# main_full_64.net
KiCad netlist of a schematic drawn in EAGLE
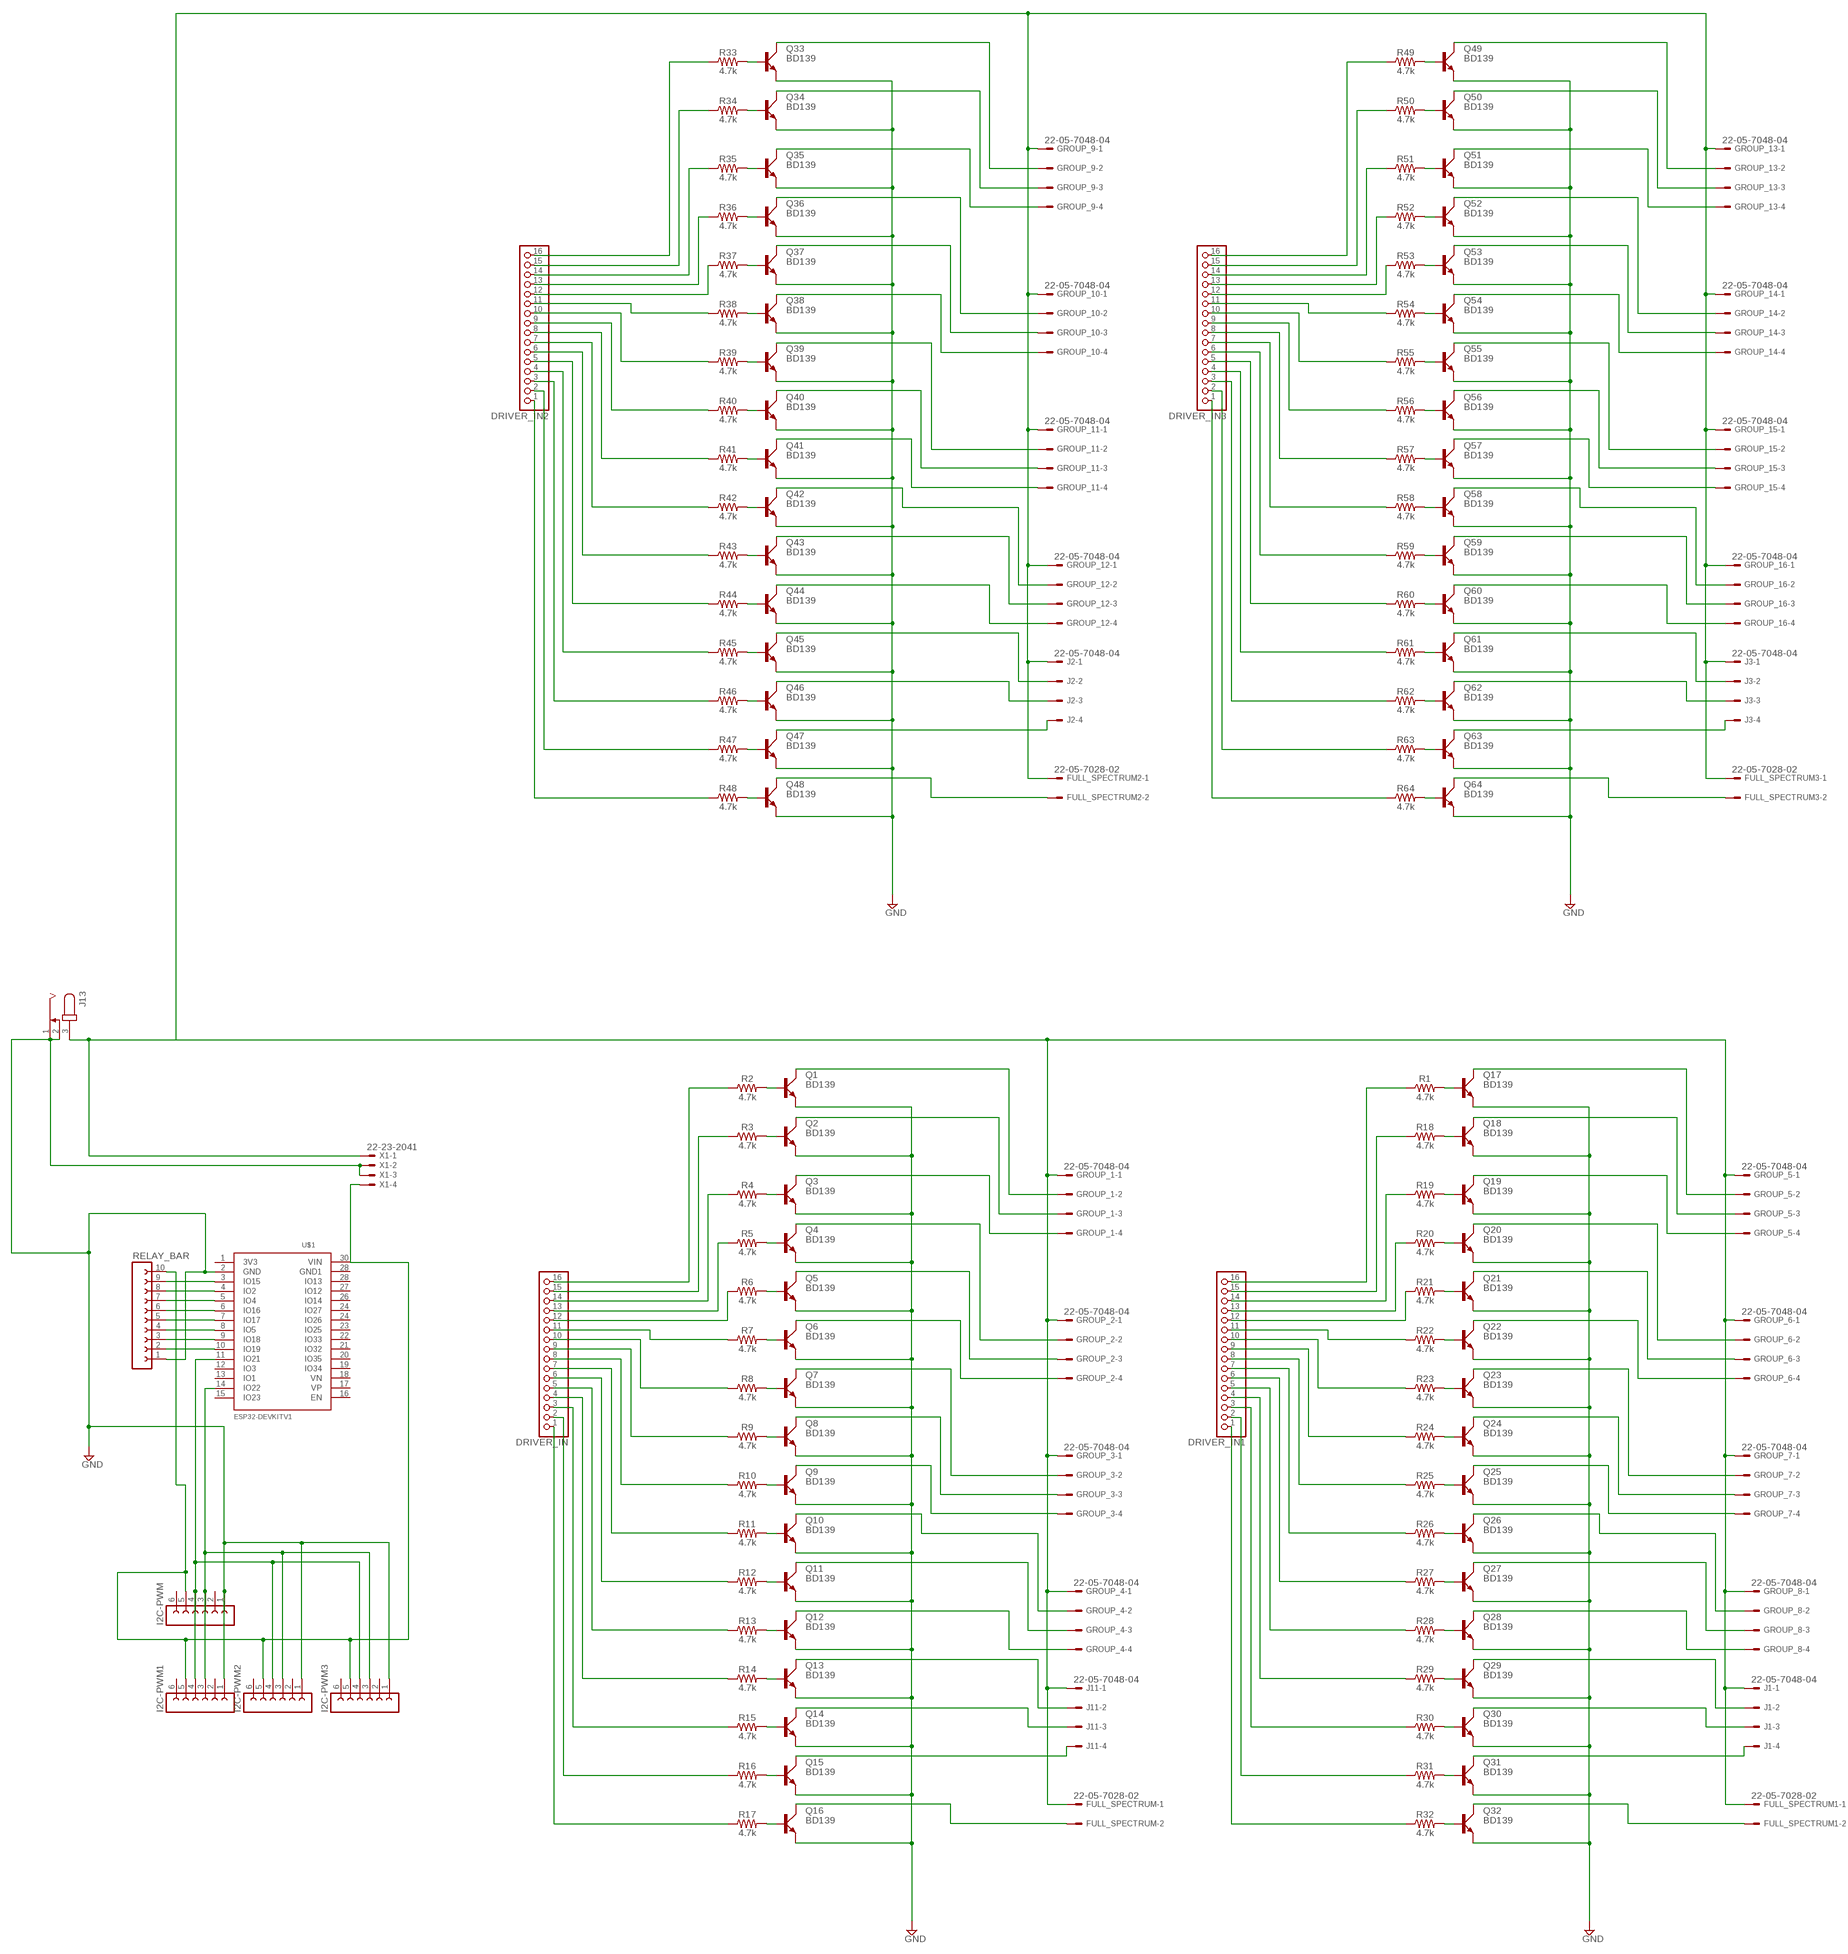
[diagram p0: schematic, sheet 1]

(export (version "E")
  (design (tool "Eeschema 10.0.6"))
  (components
    (comp (ref "DRIVER_IN")
      (value "PINHD-1X16/90")
      (footprint "eagle-import:1X16_90")
      (libsource (lib "eagle-import") (part "PINHD-1X16/90"))
    )
    (comp (ref "DRIVER_IN1")
      (value "PINHD-1X16/90")
      (footprint "eagle-import:1X16_90")
      (libsource (lib "eagle-import") (part "PINHD-1X16/90"))
    )
    (comp (ref "DRIVER_IN2")
      (value "PINHD-1X16/90")
      (footprint "eagle-import:1X16_90")
      (libsource (lib "eagle-import") (part "PINHD-1X16/90"))
    )
    (comp (ref "DRIVER_IN3")
      (value "PINHD-1X16/90")
      (footprint "eagle-import:1X16_90")
      (libsource (lib "eagle-import") (part "PINHD-1X16/90"))
    )
    (comp (ref "FULL_SPECTRUM")
      (value "22-05-7028-02")
      (footprint "eagle-import:7395-02")
      (fields (field (name "MF") "MOLEX"))
      (libsource (lib "eagle-import") (part "22-?-0205-7028"))
    )
    (comp (ref "FULL_SPECTRUM1")
      (value "22-05-7028-02")
      (footprint "eagle-import:7395-02")
      (fields (field (name "MF") "MOLEX"))
      (libsource (lib "eagle-import") (part "22-?-0205-7028"))
    )
    (comp (ref "FULL_SPECTRUM2")
      (value "22-05-7028-02")
      (footprint "eagle-import:7395-02")
      (fields (field (name "MF") "MOLEX"))
      (libsource (lib "eagle-import") (part "22-?-0205-7028"))
    )
    (comp (ref "FULL_SPECTRUM3")
      (value "22-05-7028-02")
      (footprint "eagle-import:7395-02")
      (fields (field (name "MF") "MOLEX"))
      (libsource (lib "eagle-import") (part "22-?-0205-7028"))
    )
    (comp (ref "GROUP_1")
      (value "22-05-7048-04")
      (footprint "eagle-import:7395-04")
      (fields (field (name "MF") "MOLEX"))
      (libsource (lib "eagle-import") (part "22-?-0405-7048"))
    )
    (comp (ref "GROUP_2")
      (value "22-05-7048-04")
      (footprint "eagle-import:7395-04")
      (fields (field (name "MF") "MOLEX"))
      (libsource (lib "eagle-import") (part "22-?-0405-7048"))
    )
    (comp (ref "GROUP_3")
      (value "22-05-7048-04")
      (footprint "eagle-import:7395-04")
      (fields (field (name "MF") "MOLEX"))
      (libsource (lib "eagle-import") (part "22-?-0405-7048"))
    )
    (comp (ref "GROUP_4")
      (value "22-05-7048-04")
      (footprint "eagle-import:7395-04")
      (fields (field (name "MF") "MOLEX"))
      (libsource (lib "eagle-import") (part "22-?-0405-7048"))
    )
    (comp (ref "GROUP_5")
      (value "22-05-7048-04")
      (footprint "eagle-import:7395-04")
      (fields (field (name "MF") "MOLEX"))
      (libsource (lib "eagle-import") (part "22-?-0405-7048"))
    )
    (comp (ref "GROUP_6")
      (value "22-05-7048-04")
      (footprint "eagle-import:7395-04")
      (fields (field (name "MF") "MOLEX"))
      (libsource (lib "eagle-import") (part "22-?-0405-7048"))
    )
    (comp (ref "GROUP_7")
      (value "22-05-7048-04")
      (footprint "eagle-import:7395-04")
      (fields (field (name "MF") "MOLEX"))
      (libsource (lib "eagle-import") (part "22-?-0405-7048"))
    )
    (comp (ref "GROUP_8")
      (value "22-05-7048-04")
      (footprint "eagle-import:7395-04")
      (fields (field (name "MF") "MOLEX"))
      (libsource (lib "eagle-import") (part "22-?-0405-7048"))
    )
    (comp (ref "GROUP_9")
      (value "22-05-7048-04")
      (footprint "eagle-import:7395-04")
      (fields (field (name "MF") "MOLEX"))
      (libsource (lib "eagle-import") (part "22-?-0405-7048"))
    )
    (comp (ref "GROUP_10")
      (value "22-05-7048-04")
      (footprint "eagle-import:7395-04")
      (fields (field (name "MF") "MOLEX"))
      (libsource (lib "eagle-import") (part "22-?-0405-7048"))
    )
    (comp (ref "GROUP_11")
      (value "22-05-7048-04")
      (footprint "eagle-import:7395-04")
      (fields (field (name "MF") "MOLEX"))
      (libsource (lib "eagle-import") (part "22-?-0405-7048"))
    )
    (comp (ref "GROUP_12")
      (value "22-05-7048-04")
      (footprint "eagle-import:7395-04")
      (fields (field (name "MF") "MOLEX"))
      (libsource (lib "eagle-import") (part "22-?-0405-7048"))
    )
    (comp (ref "GROUP_13")
      (value "22-05-7048-04")
      (footprint "eagle-import:7395-04")
      (fields (field (name "MF") "MOLEX"))
      (libsource (lib "eagle-import") (part "22-?-0405-7048"))
    )
    (comp (ref "GROUP_14")
      (value "22-05-7048-04")
      (footprint "eagle-import:7395-04")
      (fields (field (name "MF") "MOLEX"))
      (libsource (lib "eagle-import") (part "22-?-0405-7048"))
    )
    (comp (ref "GROUP_15")
      (value "22-05-7048-04")
      (footprint "eagle-import:7395-04")
      (fields (field (name "MF") "MOLEX"))
      (libsource (lib "eagle-import") (part "22-?-0405-7048"))
    )
    (comp (ref "GROUP_16")
      (value "22-05-7048-04")
      (footprint "eagle-import:7395-04")
      (fields (field (name "MF") "MOLEX"))
      (libsource (lib "eagle-import") (part "22-?-0405-7048"))
    )
    (comp (ref "I2C-PWM")
      (value "FE06W")
      (footprint "eagle-import:FE06W")
      (libsource (lib "eagle-import") (part "FE06W"))
    )
    (comp (ref "I2C-PWM1")
      (value "FE06W")
      (footprint "eagle-import:FE06W")
      (libsource (lib "eagle-import") (part "FE06W"))
    )
    (comp (ref "I2C-PWM2")
      (value "FE06W")
      (footprint "eagle-import:FE06W")
      (libsource (lib "eagle-import") (part "FE06W"))
    )
    (comp (ref "I2C-PWM3")
      (value "FE06W")
      (footprint "eagle-import:FE06W")
      (libsource (lib "eagle-import") (part "FE06W"))
    )
    (comp (ref "J1")
      (value "22-05-7048-04")
      (footprint "eagle-import:7395-04")
      (fields (field (name "MF") "MOLEX"))
      (libsource (lib "eagle-import") (part "22-?-0405-7048"))
    )
    (comp (ref "J2")
      (value "22-05-7048-04")
      (footprint "eagle-import:7395-04")
      (fields (field (name "MF") "MOLEX"))
      (libsource (lib "eagle-import") (part "22-?-0405-7048"))
    )
    (comp (ref "J3")
      (value "22-05-7048-04")
      (footprint "eagle-import:7395-04")
      (fields (field (name "MF") "MOLEX"))
      (libsource (lib "eagle-import") (part "22-?-0405-7048"))
    )
    (comp (ref "J11")
      (value "22-05-7048-04")
      (footprint "eagle-import:7395-04")
      (fields (field (name "MF") "MOLEX"))
      (libsource (lib "eagle-import") (part "22-?-0405-7048"))
    )
    (comp (ref "J13")
      (value "JACK-PLUG0")
      (footprint "eagle-import:SPC4077")
      (libsource (lib "eagle-import") (part "JACK-PLUG0"))
    )
    (comp (ref "Q1")
      (value "BD139")
      (footprint "eagle-import:TO126AV")
      (libsource (lib "eagle-import") (part "BD139"))
    )
    (comp (ref "Q2")
      (value "BD139")
      (footprint "eagle-import:TO126AV")
      (libsource (lib "eagle-import") (part "BD139"))
    )
    (comp (ref "Q3")
      (value "BD139")
      (footprint "eagle-import:TO126AV")
      (libsource (lib "eagle-import") (part "BD139"))
    )
    (comp (ref "Q4")
      (value "BD139")
      (footprint "eagle-import:TO126AV")
      (libsource (lib "eagle-import") (part "BD139"))
    )
    (comp (ref "Q5")
      (value "BD139")
      (footprint "eagle-import:TO126AV")
      (libsource (lib "eagle-import") (part "BD139"))
    )
    (comp (ref "Q6")
      (value "BD139")
      (footprint "eagle-import:TO126AV")
      (libsource (lib "eagle-import") (part "BD139"))
    )
    (comp (ref "Q7")
      (value "BD139")
      (footprint "eagle-import:TO126AV")
      (libsource (lib "eagle-import") (part "BD139"))
    )
    (comp (ref "Q8")
      (value "BD139")
      (footprint "eagle-import:TO126AV")
      (libsource (lib "eagle-import") (part "BD139"))
    )
    (comp (ref "Q9")
      (value "BD139")
      (footprint "eagle-import:TO126AV")
      (libsource (lib "eagle-import") (part "BD139"))
    )
    (comp (ref "Q10")
      (value "BD139")
      (footprint "eagle-import:TO126AV")
      (libsource (lib "eagle-import") (part "BD139"))
    )
    (comp (ref "Q11")
      (value "BD139")
      (footprint "eagle-import:TO126AV")
      (libsource (lib "eagle-import") (part "BD139"))
    )
    (comp (ref "Q12")
      (value "BD139")
      (footprint "eagle-import:TO126AV")
      (libsource (lib "eagle-import") (part "BD139"))
    )
    (comp (ref "Q13")
      (value "BD139")
      (footprint "eagle-import:TO126AV")
      (libsource (lib "eagle-import") (part "BD139"))
    )
    (comp (ref "Q14")
      (value "BD139")
      (footprint "eagle-import:TO126AV")
      (libsource (lib "eagle-import") (part "BD139"))
    )
    (comp (ref "Q15")
      (value "BD139")
      (footprint "eagle-import:TO126AV")
      (libsource (lib "eagle-import") (part "BD139"))
    )
    (comp (ref "Q16")
      (value "BD139")
      (footprint "eagle-import:TO126AV")
      (libsource (lib "eagle-import") (part "BD139"))
    )
    (comp (ref "Q17")
      (value "BD139")
      (footprint "eagle-import:TO126AV")
      (libsource (lib "eagle-import") (part "BD139"))
    )
    (comp (ref "Q18")
      (value "BD139")
      (footprint "eagle-import:TO126AV")
      (libsource (lib "eagle-import") (part "BD139"))
    )
    (comp (ref "Q19")
      (value "BD139")
      (footprint "eagle-import:TO126AV")
      (libsource (lib "eagle-import") (part "BD139"))
    )
    (comp (ref "Q20")
      (value "BD139")
      (footprint "eagle-import:TO126AV")
      (libsource (lib "eagle-import") (part "BD139"))
    )
    (comp (ref "Q21")
      (value "BD139")
      (footprint "eagle-import:TO126AV")
      (libsource (lib "eagle-import") (part "BD139"))
    )
    (comp (ref "Q22")
      (value "BD139")
      (footprint "eagle-import:TO126AV")
      (libsource (lib "eagle-import") (part "BD139"))
    )
    (comp (ref "Q23")
      (value "BD139")
      (footprint "eagle-import:TO126AV")
      (libsource (lib "eagle-import") (part "BD139"))
    )
    (comp (ref "Q24")
      (value "BD139")
      (footprint "eagle-import:TO126AV")
      (libsource (lib "eagle-import") (part "BD139"))
    )
    (comp (ref "Q25")
      (value "BD139")
      (footprint "eagle-import:TO126AV")
      (libsource (lib "eagle-import") (part "BD139"))
    )
    (comp (ref "Q26")
      (value "BD139")
      (footprint "eagle-import:TO126AV")
      (libsource (lib "eagle-import") (part "BD139"))
    )
    (comp (ref "Q27")
      (value "BD139")
      (footprint "eagle-import:TO126AV")
      (libsource (lib "eagle-import") (part "BD139"))
    )
    (comp (ref "Q28")
      (value "BD139")
      (footprint "eagle-import:TO126AV")
      (libsource (lib "eagle-import") (part "BD139"))
    )
    (comp (ref "Q29")
      (value "BD139")
      (footprint "eagle-import:TO126AV")
      (libsource (lib "eagle-import") (part "BD139"))
    )
    (comp (ref "Q30")
      (value "BD139")
      (footprint "eagle-import:TO126AV")
      (libsource (lib "eagle-import") (part "BD139"))
    )
    (comp (ref "Q31")
      (value "BD139")
      (footprint "eagle-import:TO126AV")
      (libsource (lib "eagle-import") (part "BD139"))
    )
    (comp (ref "Q32")
      (value "BD139")
      (footprint "eagle-import:TO126AV")
      (libsource (lib "eagle-import") (part "BD139"))
    )
    (comp (ref "Q33")
      (value "BD139")
      (footprint "eagle-import:TO126AV")
      (libsource (lib "eagle-import") (part "BD139"))
    )
    (comp (ref "Q34")
      (value "BD139")
      (footprint "eagle-import:TO126AV")
      (libsource (lib "eagle-import") (part "BD139"))
    )
    (comp (ref "Q35")
      (value "BD139")
      (footprint "eagle-import:TO126AV")
      (libsource (lib "eagle-import") (part "BD139"))
    )
    (comp (ref "Q36")
      (value "BD139")
      (footprint "eagle-import:TO126AV")
      (libsource (lib "eagle-import") (part "BD139"))
    )
    (comp (ref "Q37")
      (value "BD139")
      (footprint "eagle-import:TO126AV")
      (libsource (lib "eagle-import") (part "BD139"))
    )
    (comp (ref "Q38")
      (value "BD139")
      (footprint "eagle-import:TO126AV")
      (libsource (lib "eagle-import") (part "BD139"))
    )
    (comp (ref "Q39")
      (value "BD139")
      (footprint "eagle-import:TO126AV")
      (libsource (lib "eagle-import") (part "BD139"))
    )
    (comp (ref "Q40")
      (value "BD139")
      (footprint "eagle-import:TO126AV")
      (libsource (lib "eagle-import") (part "BD139"))
    )
    (comp (ref "Q41")
      (value "BD139")
      (footprint "eagle-import:TO126AV")
      (libsource (lib "eagle-import") (part "BD139"))
    )
    (comp (ref "Q42")
      (value "BD139")
      (footprint "eagle-import:TO126AV")
      (libsource (lib "eagle-import") (part "BD139"))
    )
    (comp (ref "Q43")
      (value "BD139")
      (footprint "eagle-import:TO126AV")
      (libsource (lib "eagle-import") (part "BD139"))
    )
    (comp (ref "Q44")
      (value "BD139")
      (footprint "eagle-import:TO126AV")
      (libsource (lib "eagle-import") (part "BD139"))
    )
    (comp (ref "Q45")
      (value "BD139")
      (footprint "eagle-import:TO126AV")
      (libsource (lib "eagle-import") (part "BD139"))
    )
    (comp (ref "Q46")
      (value "BD139")
      (footprint "eagle-import:TO126AV")
      (libsource (lib "eagle-import") (part "BD139"))
    )
    (comp (ref "Q47")
      (value "BD139")
      (footprint "eagle-import:TO126AV")
      (libsource (lib "eagle-import") (part "BD139"))
    )
    (comp (ref "Q48")
      (value "BD139")
      (footprint "eagle-import:TO126AV")
      (libsource (lib "eagle-import") (part "BD139"))
    )
    (comp (ref "Q49")
      (value "BD139")
      (footprint "eagle-import:TO126AV")
      (libsource (lib "eagle-import") (part "BD139"))
    )
    (comp (ref "Q50")
      (value "BD139")
      (footprint "eagle-import:TO126AV")
      (libsource (lib "eagle-import") (part "BD139"))
    )
    (comp (ref "Q51")
      (value "BD139")
      (footprint "eagle-import:TO126AV")
      (libsource (lib "eagle-import") (part "BD139"))
    )
    (comp (ref "Q52")
      (value "BD139")
      (footprint "eagle-import:TO126AV")
      (libsource (lib "eagle-import") (part "BD139"))
    )
    (comp (ref "Q53")
      (value "BD139")
      (footprint "eagle-import:TO126AV")
      (libsource (lib "eagle-import") (part "BD139"))
    )
    (comp (ref "Q54")
      (value "BD139")
      (footprint "eagle-import:TO126AV")
      (libsource (lib "eagle-import") (part "BD139"))
    )
    (comp (ref "Q55")
      (value "BD139")
      (footprint "eagle-import:TO126AV")
      (libsource (lib "eagle-import") (part "BD139"))
    )
    (comp (ref "Q56")
      (value "BD139")
      (footprint "eagle-import:TO126AV")
      (libsource (lib "eagle-import") (part "BD139"))
    )
    (comp (ref "Q57")
      (value "BD139")
      (footprint "eagle-import:TO126AV")
      (libsource (lib "eagle-import") (part "BD139"))
    )
    (comp (ref "Q58")
      (value "BD139")
      (footprint "eagle-import:TO126AV")
      (libsource (lib "eagle-import") (part "BD139"))
    )
    (comp (ref "Q59")
      (value "BD139")
      (footprint "eagle-import:TO126AV")
      (libsource (lib "eagle-import") (part "BD139"))
    )
    (comp (ref "Q60")
      (value "BD139")
      (footprint "eagle-import:TO126AV")
      (libsource (lib "eagle-import") (part "BD139"))
    )
    (comp (ref "Q61")
      (value "BD139")
      (footprint "eagle-import:TO126AV")
      (libsource (lib "eagle-import") (part "BD139"))
    )
    (comp (ref "Q62")
      (value "BD139")
      (footprint "eagle-import:TO126AV")
      (libsource (lib "eagle-import") (part "BD139"))
    )
    (comp (ref "Q63")
      (value "BD139")
      (footprint "eagle-import:TO126AV")
      (libsource (lib "eagle-import") (part "BD139"))
    )
    (comp (ref "Q64")
      (value "BD139")
      (footprint "eagle-import:TO126AV")
      (libsource (lib "eagle-import") (part "BD139"))
    )
    (comp (ref "R1")
      (value "4.7k")
      (footprint "eagle-import:0603")
      (libsource (lib "eagle-import") (part "4.7KOHM-0603-1/10W-1%"))
    )
    (comp (ref "R2")
      (value "4.7k")
      (footprint "eagle-import:0603")
      (libsource (lib "eagle-import") (part "4.7KOHM-0603-1/10W-1%"))
    )
    (comp (ref "R3")
      (value "4.7k")
      (footprint "eagle-import:0603")
      (libsource (lib "eagle-import") (part "4.7KOHM-0603-1/10W-1%"))
    )
    (comp (ref "R4")
      (value "4.7k")
      (footprint "eagle-import:0603")
      (libsource (lib "eagle-import") (part "4.7KOHM-0603-1/10W-1%"))
    )
    (comp (ref "R5")
      (value "4.7k")
      (footprint "eagle-import:0603")
      (libsource (lib "eagle-import") (part "4.7KOHM-0603-1/10W-1%"))
    )
    (comp (ref "R6")
      (value "4.7k")
      (footprint "eagle-import:0603")
      (libsource (lib "eagle-import") (part "4.7KOHM-0603-1/10W-1%"))
    )
    (comp (ref "R7")
      (value "4.7k")
      (footprint "eagle-import:0603")
      (libsource (lib "eagle-import") (part "4.7KOHM-0603-1/10W-1%"))
    )
    (comp (ref "R8")
      (value "4.7k")
      (footprint "eagle-import:0603")
      (libsource (lib "eagle-import") (part "4.7KOHM-0603-1/10W-1%"))
    )
    (comp (ref "R9")
      (value "4.7k")
      (footprint "eagle-import:0603")
      (libsource (lib "eagle-import") (part "4.7KOHM-0603-1/10W-1%"))
    )
    (comp (ref "R10")
      (value "4.7k")
      (footprint "eagle-import:0603")
      (libsource (lib "eagle-import") (part "4.7KOHM-0603-1/10W-1%"))
    )
    (comp (ref "R11")
      (value "4.7k")
      (footprint "eagle-import:0603")
      (libsource (lib "eagle-import") (part "4.7KOHM-0603-1/10W-1%"))
    )
    (comp (ref "R12")
      (value "4.7k")
      (footprint "eagle-import:0603")
      (libsource (lib "eagle-import") (part "4.7KOHM-0603-1/10W-1%"))
    )
    (comp (ref "R13")
      (value "4.7k")
      (footprint "eagle-import:0603")
      (libsource (lib "eagle-import") (part "4.7KOHM-0603-1/10W-1%"))
    )
    (comp (ref "R14")
      (value "4.7k")
      (footprint "eagle-import:0603")
      (libsource (lib "eagle-import") (part "4.7KOHM-0603-1/10W-1%"))
    )
    (comp (ref "R15")
      (value "4.7k")
      (footprint "eagle-import:0603")
      (libsource (lib "eagle-import") (part "4.7KOHM-0603-1/10W-1%"))
    )
    (comp (ref "R16")
      (value "4.7k")
      (footprint "eagle-import:0603")
      (libsource (lib "eagle-import") (part "4.7KOHM-0603-1/10W-1%"))
    )
    (comp (ref "R17")
      (value "4.7k")
      (footprint "eagle-import:0603")
      (libsource (lib "eagle-import") (part "4.7KOHM-0603-1/10W-1%"))
    )
    (comp (ref "R18")
      (value "4.7k")
      (footprint "eagle-import:0603")
      (libsource (lib "eagle-import") (part "4.7KOHM-0603-1/10W-1%"))
    )
    (comp (ref "R19")
      (value "4.7k")
      (footprint "eagle-import:0603")
      (libsource (lib "eagle-import") (part "4.7KOHM-0603-1/10W-1%"))
    )
    (comp (ref "R20")
      (value "4.7k")
      (footprint "eagle-import:0603")
      (libsource (lib "eagle-import") (part "4.7KOHM-0603-1/10W-1%"))
    )
    (comp (ref "R21")
      (value "4.7k")
      (footprint "eagle-import:0603")
      (libsource (lib "eagle-import") (part "4.7KOHM-0603-1/10W-1%"))
    )
    (comp (ref "R22")
      (value "4.7k")
      (footprint "eagle-import:0603")
      (libsource (lib "eagle-import") (part "4.7KOHM-0603-1/10W-1%"))
    )
    (comp (ref "R23")
      (value "4.7k")
      (footprint "eagle-import:0603")
      (libsource (lib "eagle-import") (part "4.7KOHM-0603-1/10W-1%"))
    )
    (comp (ref "R24")
      (value "4.7k")
      (footprint "eagle-import:0603")
      (libsource (lib "eagle-import") (part "4.7KOHM-0603-1/10W-1%"))
    )
    (comp (ref "R25")
      (value "4.7k")
      (footprint "eagle-import:0603")
      (libsource (lib "eagle-import") (part "4.7KOHM-0603-1/10W-1%"))
    )
    (comp (ref "R26")
      (value "4.7k")
      (footprint "eagle-import:0603")
      (libsource (lib "eagle-import") (part "4.7KOHM-0603-1/10W-1%"))
    )
    (comp (ref "R27")
      (value "4.7k")
      (footprint "eagle-import:0603")
      (libsource (lib "eagle-import") (part "4.7KOHM-0603-1/10W-1%"))
    )
    (comp (ref "R28")
      (value "4.7k")
      (footprint "eagle-import:0603")
      (libsource (lib "eagle-import") (part "4.7KOHM-0603-1/10W-1%"))
    )
    (comp (ref "R29")
      (value "4.7k")
      (footprint "eagle-import:0603")
      (libsource (lib "eagle-import") (part "4.7KOHM-0603-1/10W-1%"))
    )
    (comp (ref "R30")
      (value "4.7k")
      (footprint "eagle-import:0603")
      (libsource (lib "eagle-import") (part "4.7KOHM-0603-1/10W-1%"))
    )
    (comp (ref "R31")
      (value "4.7k")
      (footprint "eagle-import:0603")
      (libsource (lib "eagle-import") (part "4.7KOHM-0603-1/10W-1%"))
    )
    (comp (ref "R32")
      (value "4.7k")
      (footprint "eagle-import:0603")
      (libsource (lib "eagle-import") (part "4.7KOHM-0603-1/10W-1%"))
    )
    (comp (ref "R33")
      (value "4.7k")
      (footprint "eagle-import:0603")
      (libsource (lib "eagle-import") (part "4.7KOHM-0603-1/10W-1%"))
    )
    (comp (ref "R34")
      (value "4.7k")
      (footprint "eagle-import:0603")
      (libsource (lib "eagle-import") (part "4.7KOHM-0603-1/10W-1%"))
    )
    (comp (ref "R35")
      (value "4.7k")
      (footprint "eagle-import:0603")
      (libsource (lib "eagle-import") (part "4.7KOHM-0603-1/10W-1%"))
    )
    (comp (ref "R36")
      (value "4.7k")
      (footprint "eagle-import:0603")
      (libsource (lib "eagle-import") (part "4.7KOHM-0603-1/10W-1%"))
    )
    (comp (ref "R37")
      (value "4.7k")
      (footprint "eagle-import:0603")
      (libsource (lib "eagle-import") (part "4.7KOHM-0603-1/10W-1%"))
    )
    (comp (ref "R38")
      (value "4.7k")
      (footprint "eagle-import:0603")
      (libsource (lib "eagle-import") (part "4.7KOHM-0603-1/10W-1%"))
    )
    (comp (ref "R39")
      (value "4.7k")
      (footprint "eagle-import:0603")
      (libsource (lib "eagle-import") (part "4.7KOHM-0603-1/10W-1%"))
    )
    (comp (ref "R40")
      (value "4.7k")
      (footprint "eagle-import:0603")
      (libsource (lib "eagle-import") (part "4.7KOHM-0603-1/10W-1%"))
    )
    (comp (ref "R41")
      (value "4.7k")
      (footprint "eagle-import:0603")
      (libsource (lib "eagle-import") (part "4.7KOHM-0603-1/10W-1%"))
    )
    (comp (ref "R42")
      (value "4.7k")
      (footprint "eagle-import:0603")
      (libsource (lib "eagle-import") (part "4.7KOHM-0603-1/10W-1%"))
    )
    (comp (ref "R43")
      (value "4.7k")
      (footprint "eagle-import:0603")
      (libsource (lib "eagle-import") (part "4.7KOHM-0603-1/10W-1%"))
    )
    (comp (ref "R44")
      (value "4.7k")
      (footprint "eagle-import:0603")
      (libsource (lib "eagle-import") (part "4.7KOHM-0603-1/10W-1%"))
    )
    (comp (ref "R45")
      (value "4.7k")
      (footprint "eagle-import:0603")
      (libsource (lib "eagle-import") (part "4.7KOHM-0603-1/10W-1%"))
    )
    (comp (ref "R46")
      (value "4.7k")
      (footprint "eagle-import:0603")
      (libsource (lib "eagle-import") (part "4.7KOHM-0603-1/10W-1%"))
    )
    (comp (ref "R47")
      (value "4.7k")
      (footprint "eagle-import:0603")
      (libsource (lib "eagle-import") (part "4.7KOHM-0603-1/10W-1%"))
    )
    (comp (ref "R48")
      (value "4.7k")
      (footprint "eagle-import:0603")
      (libsource (lib "eagle-import") (part "4.7KOHM-0603-1/10W-1%"))
    )
    (comp (ref "R49")
      (value "4.7k")
      (footprint "eagle-import:0603")
      (libsource (lib "eagle-import") (part "4.7KOHM-0603-1/10W-1%"))
    )
    (comp (ref "R50")
      (value "4.7k")
      (footprint "eagle-import:0603")
      (libsource (lib "eagle-import") (part "4.7KOHM-0603-1/10W-1%"))
    )
    (comp (ref "R51")
      (value "4.7k")
      (footprint "eagle-import:0603")
      (libsource (lib "eagle-import") (part "4.7KOHM-0603-1/10W-1%"))
    )
    (comp (ref "R52")
      (value "4.7k")
      (footprint "eagle-import:0603")
      (libsource (lib "eagle-import") (part "4.7KOHM-0603-1/10W-1%"))
    )
    (comp (ref "R53")
      (value "4.7k")
      (footprint "eagle-import:0603")
      (libsource (lib "eagle-import") (part "4.7KOHM-0603-1/10W-1%"))
    )
    (comp (ref "R54")
      (value "4.7k")
      (footprint "eagle-import:0603")
      (libsource (lib "eagle-import") (part "4.7KOHM-0603-1/10W-1%"))
    )
    (comp (ref "R55")
      (value "4.7k")
      (footprint "eagle-import:0603")
      (libsource (lib "eagle-import") (part "4.7KOHM-0603-1/10W-1%"))
    )
    (comp (ref "R56")
      (value "4.7k")
      (footprint "eagle-import:0603")
      (libsource (lib "eagle-import") (part "4.7KOHM-0603-1/10W-1%"))
    )
    (comp (ref "R57")
      (value "4.7k")
      (footprint "eagle-import:0603")
      (libsource (lib "eagle-import") (part "4.7KOHM-0603-1/10W-1%"))
    )
    (comp (ref "R58")
      (value "4.7k")
      (footprint "eagle-import:0603")
      (libsource (lib "eagle-import") (part "4.7KOHM-0603-1/10W-1%"))
    )
    (comp (ref "R59")
      (value "4.7k")
      (footprint "eagle-import:0603")
      (libsource (lib "eagle-import") (part "4.7KOHM-0603-1/10W-1%"))
    )
    (comp (ref "R60")
      (value "4.7k")
      (footprint "eagle-import:0603")
      (libsource (lib "eagle-import") (part "4.7KOHM-0603-1/10W-1%"))
    )
    (comp (ref "R61")
      (value "4.7k")
      (footprint "eagle-import:0603")
      (libsource (lib "eagle-import") (part "4.7KOHM-0603-1/10W-1%"))
    )
    (comp (ref "R62")
      (value "4.7k")
      (footprint "eagle-import:0603")
      (libsource (lib "eagle-import") (part "4.7KOHM-0603-1/10W-1%"))
    )
    (comp (ref "R63")
      (value "4.7k")
      (footprint "eagle-import:0603")
      (libsource (lib "eagle-import") (part "4.7KOHM-0603-1/10W-1%"))
    )
    (comp (ref "R64")
      (value "4.7k")
      (footprint "eagle-import:0603")
      (libsource (lib "eagle-import") (part "4.7KOHM-0603-1/10W-1%"))
    )
    (comp (ref "RELAY_BAR")
      (value "FE10W")
      (footprint "eagle-import:FE10W")
      (libsource (lib "eagle-import") (part "FE10W"))
    )
    (comp (ref "U$1")
      (value "ESP32DEVKITV1")
      (footprint "eagle-import:ESP32-DEVKITV1")
      (libsource (lib "eagle-import") (part "ESP32DEVKITV1"))
    )
    (comp (ref "X1")
      (value "22-23-2041")
      (footprint "eagle-import:22-23-2041")
      (fields (field (name "MF") "MOLEX"))
      (libsource (lib "eagle-import") (part "22-23-2041"))
    )
  )
  (nets
    (net (code "1") (name "GND") (class "Default")
      (node (ref "I2C-PWM") (pin "1") (pinfunction "1_1") (pintype "passive"))
      (node (ref "I2C-PWM1") (pin "1") (pinfunction "1_1") (pintype "passive"))
      (node (ref "I2C-PWM2") (pin "1") (pinfunction "1_1") (pintype "passive"))
      (node (ref "I2C-PWM3") (pin "1") (pinfunction "1_1") (pintype "passive"))
      (node (ref "J13") (pin "1") (pinfunction "1_1") (pintype "passive"))
      (node (ref "J13") (pin "2") (pinfunction "2_2") (pintype "passive"))
      (node (ref "Q1") (pin "E") (pinfunction "E_E") (pintype "passive"))
      (node (ref "Q10") (pin "E") (pinfunction "E_E") (pintype "passive"))
      (node (ref "Q11") (pin "E") (pinfunction "E_E") (pintype "passive"))
      (node (ref "Q12") (pin "E") (pinfunction "E_E") (pintype "passive"))
      (node (ref "Q13") (pin "E") (pinfunction "E_E") (pintype "passive"))
      (node (ref "Q14") (pin "E") (pinfunction "E_E") (pintype "passive"))
      (node (ref "Q15") (pin "E") (pinfunction "E_E") (pintype "passive"))
      (node (ref "Q16") (pin "E") (pinfunction "E_E") (pintype "passive"))
      (node (ref "Q17") (pin "E") (pinfunction "E_E") (pintype "passive"))
      (node (ref "Q18") (pin "E") (pinfunction "E_E") (pintype "passive"))
      (node (ref "Q19") (pin "E") (pinfunction "E_E") (pintype "passive"))
      (node (ref "Q2") (pin "E") (pinfunction "E_E") (pintype "passive"))
      (node (ref "Q20") (pin "E") (pinfunction "E_E") (pintype "passive"))
      (node (ref "Q21") (pin "E") (pinfunction "E_E") (pintype "passive"))
      (node (ref "Q22") (pin "E") (pinfunction "E_E") (pintype "passive"))
      (node (ref "Q23") (pin "E") (pinfunction "E_E") (pintype "passive"))
      (node (ref "Q24") (pin "E") (pinfunction "E_E") (pintype "passive"))
      (node (ref "Q25") (pin "E") (pinfunction "E_E") (pintype "passive"))
      (node (ref "Q26") (pin "E") (pinfunction "E_E") (pintype "passive"))
      (node (ref "Q27") (pin "E") (pinfunction "E_E") (pintype "passive"))
      (node (ref "Q28") (pin "E") (pinfunction "E_E") (pintype "passive"))
      (node (ref "Q29") (pin "E") (pinfunction "E_E") (pintype "passive"))
      (node (ref "Q3") (pin "E") (pinfunction "E_E") (pintype "passive"))
      (node (ref "Q30") (pin "E") (pinfunction "E_E") (pintype "passive"))
      (node (ref "Q31") (pin "E") (pinfunction "E_E") (pintype "passive"))
      (node (ref "Q32") (pin "E") (pinfunction "E_E") (pintype "passive"))
      (node (ref "Q33") (pin "E") (pinfunction "E_E") (pintype "passive"))
      (node (ref "Q34") (pin "E") (pinfunction "E_E") (pintype "passive"))
      (node (ref "Q35") (pin "E") (pinfunction "E_E") (pintype "passive"))
      (node (ref "Q36") (pin "E") (pinfunction "E_E") (pintype "passive"))
      (node (ref "Q37") (pin "E") (pinfunction "E_E") (pintype "passive"))
      (node (ref "Q38") (pin "E") (pinfunction "E_E") (pintype "passive"))
      (node (ref "Q39") (pin "E") (pinfunction "E_E") (pintype "passive"))
      (node (ref "Q4") (pin "E") (pinfunction "E_E") (pintype "passive"))
      (node (ref "Q40") (pin "E") (pinfunction "E_E") (pintype "passive"))
      (node (ref "Q41") (pin "E") (pinfunction "E_E") (pintype "passive"))
      (node (ref "Q42") (pin "E") (pinfunction "E_E") (pintype "passive"))
      (node (ref "Q43") (pin "E") (pinfunction "E_E") (pintype "passive"))
      (node (ref "Q44") (pin "E") (pinfunction "E_E") (pintype "passive"))
      (node (ref "Q45") (pin "E") (pinfunction "E_E") (pintype "passive"))
      (node (ref "Q46") (pin "E") (pinfunction "E_E") (pintype "passive"))
      (node (ref "Q47") (pin "E") (pinfunction "E_E") (pintype "passive"))
      (node (ref "Q48") (pin "E") (pinfunction "E_E") (pintype "passive"))
      (node (ref "Q49") (pin "E") (pinfunction "E_E") (pintype "passive"))
      (node (ref "Q5") (pin "E") (pinfunction "E_E") (pintype "passive"))
      (node (ref "Q50") (pin "E") (pinfunction "E_E") (pintype "passive"))
      (node (ref "Q51") (pin "E") (pinfunction "E_E") (pintype "passive"))
      (node (ref "Q52") (pin "E") (pinfunction "E_E") (pintype "passive"))
      (node (ref "Q53") (pin "E") (pinfunction "E_E") (pintype "passive"))
      (node (ref "Q54") (pin "E") (pinfunction "E_E") (pintype "passive"))
      (node (ref "Q55") (pin "E") (pinfunction "E_E") (pintype "passive"))
      (node (ref "Q56") (pin "E") (pinfunction "E_E") (pintype "passive"))
      (node (ref "Q57") (pin "E") (pinfunction "E_E") (pintype "passive"))
      (node (ref "Q58") (pin "E") (pinfunction "E_E") (pintype "passive"))
      (node (ref "Q59") (pin "E") (pinfunction "E_E") (pintype "passive"))
      (node (ref "Q6") (pin "E") (pinfunction "E_E") (pintype "passive"))
      (node (ref "Q60") (pin "E") (pinfunction "E_E") (pintype "passive"))
      (node (ref "Q61") (pin "E") (pinfunction "E_E") (pintype "passive"))
      (node (ref "Q62") (pin "E") (pinfunction "E_E") (pintype "passive"))
      (node (ref "Q63") (pin "E") (pinfunction "E_E") (pintype "passive"))
      (node (ref "Q64") (pin "E") (pinfunction "E_E") (pintype "passive"))
      (node (ref "Q7") (pin "E") (pinfunction "E_E") (pintype "passive"))
      (node (ref "Q8") (pin "E") (pinfunction "E_E") (pintype "passive"))
      (node (ref "Q9") (pin "E") (pinfunction "E_E") (pintype "passive"))
      (node (ref "RELAY_BAR") (pin "1") (pinfunction "1_1") (pintype "passive"))
      (node (ref "U$1") (pin "2") (pinfunction "GND_2") (pintype "bidirectional"))
      (node (ref "X1") (pin "2") (pinfunction "S_2") (pintype "passive"))
      (node (ref "X1") (pin "3") (pinfunction "S_3") (pintype "passive"))
    )
    (net (code "2") (name "Net-(DRIVER_IN-Pad1)") (class "Default")
      (node (ref "DRIVER_IN") (pin "1") (pinfunction "1_1") (pintype "passive"))
      (node (ref "R17") (pin "1") (pinfunction "1_1") (pintype "passive"))
    )
    (net (code "3") (name "Net-(DRIVER_IN-Pad2)") (class "Default")
      (node (ref "DRIVER_IN") (pin "2") (pinfunction "2_2") (pintype "passive"))
      (node (ref "R16") (pin "1") (pinfunction "1_1") (pintype "passive"))
    )
    (net (code "4") (name "Net-(DRIVER_IN-Pad3)") (class "Default")
      (node (ref "DRIVER_IN") (pin "3") (pinfunction "3_3") (pintype "passive"))
      (node (ref "R15") (pin "1") (pinfunction "1_1") (pintype "passive"))
    )
    (net (code "5") (name "Net-(DRIVER_IN-Pad4)") (class "Default")
      (node (ref "DRIVER_IN") (pin "4") (pinfunction "4_4") (pintype "passive"))
      (node (ref "R14") (pin "1") (pinfunction "1_1") (pintype "passive"))
    )
    (net (code "6") (name "Net-(DRIVER_IN-Pad5)") (class "Default")
      (node (ref "DRIVER_IN") (pin "5") (pinfunction "5_5") (pintype "passive"))
      (node (ref "R13") (pin "1") (pinfunction "1_1") (pintype "passive"))
    )
    (net (code "7") (name "Net-(DRIVER_IN-Pad6)") (class "Default")
      (node (ref "DRIVER_IN") (pin "6") (pinfunction "6_6") (pintype "passive"))
      (node (ref "R12") (pin "1") (pinfunction "1_1") (pintype "passive"))
    )
    (net (code "8") (name "Net-(DRIVER_IN-Pad7)") (class "Default")
      (node (ref "DRIVER_IN") (pin "7") (pinfunction "7_7") (pintype "passive"))
      (node (ref "R11") (pin "1") (pinfunction "1_1") (pintype "passive"))
    )
    (net (code "9") (name "Net-(DRIVER_IN-Pad8)") (class "Default")
      (node (ref "DRIVER_IN") (pin "8") (pinfunction "8_8") (pintype "passive"))
      (node (ref "R10") (pin "1") (pinfunction "1_1") (pintype "passive"))
    )
    (net (code "10") (name "Net-(DRIVER_IN-Pad9)") (class "Default")
      (node (ref "DRIVER_IN") (pin "9") (pinfunction "9_9") (pintype "passive"))
      (node (ref "R9") (pin "1") (pinfunction "1_1") (pintype "passive"))
    )
    (net (code "11") (name "Net-(DRIVER_IN-Pad10)") (class "Default")
      (node (ref "DRIVER_IN") (pin "10") (pinfunction "10_10") (pintype "passive"))
      (node (ref "R8") (pin "1") (pinfunction "1_1") (pintype "passive"))
    )
    (net (code "12") (name "Net-(DRIVER_IN-Pad11)") (class "Default")
      (node (ref "DRIVER_IN") (pin "11") (pinfunction "11_11") (pintype "passive"))
      (node (ref "R7") (pin "1") (pinfunction "1_1") (pintype "passive"))
    )
    (net (code "13") (name "Net-(DRIVER_IN-Pad12)") (class "Default")
      (node (ref "DRIVER_IN") (pin "12") (pinfunction "12_12") (pintype "passive"))
      (node (ref "R6") (pin "1") (pinfunction "1_1") (pintype "passive"))
    )
    (net (code "14") (name "Net-(DRIVER_IN-Pad13)") (class "Default")
      (node (ref "DRIVER_IN") (pin "13") (pinfunction "13_13") (pintype "passive"))
      (node (ref "R5") (pin "1") (pinfunction "1_1") (pintype "passive"))
    )
    (net (code "15") (name "Net-(DRIVER_IN-Pad14)") (class "Default")
      (node (ref "DRIVER_IN") (pin "14") (pinfunction "14_14") (pintype "passive"))
      (node (ref "R4") (pin "1") (pinfunction "1_1") (pintype "passive"))
    )
    (net (code "16") (name "Net-(DRIVER_IN-Pad15)") (class "Default")
      (node (ref "DRIVER_IN") (pin "15") (pinfunction "15_15") (pintype "passive"))
      (node (ref "R3") (pin "1") (pinfunction "1_1") (pintype "passive"))
    )
    (net (code "17") (name "Net-(DRIVER_IN-Pad16)") (class "Default")
      (node (ref "DRIVER_IN") (pin "16") (pinfunction "16_16") (pintype "passive"))
      (node (ref "R2") (pin "1") (pinfunction "1_1") (pintype "passive"))
    )
    (net (code "18") (name "Net-(DRIVER_IN1-Pad1)") (class "Default")
      (node (ref "DRIVER_IN1") (pin "1") (pinfunction "1_1") (pintype "passive"))
      (node (ref "R32") (pin "1") (pinfunction "1_1") (pintype "passive"))
    )
    (net (code "19") (name "Net-(DRIVER_IN1-Pad2)") (class "Default")
      (node (ref "DRIVER_IN1") (pin "2") (pinfunction "2_2") (pintype "passive"))
      (node (ref "R31") (pin "1") (pinfunction "1_1") (pintype "passive"))
    )
    (net (code "20") (name "Net-(DRIVER_IN1-Pad3)") (class "Default")
      (node (ref "DRIVER_IN1") (pin "3") (pinfunction "3_3") (pintype "passive"))
      (node (ref "R30") (pin "1") (pinfunction "1_1") (pintype "passive"))
    )
    (net (code "21") (name "Net-(DRIVER_IN1-Pad4)") (class "Default")
      (node (ref "DRIVER_IN1") (pin "4") (pinfunction "4_4") (pintype "passive"))
      (node (ref "R29") (pin "1") (pinfunction "1_1") (pintype "passive"))
    )
    (net (code "22") (name "Net-(DRIVER_IN1-Pad5)") (class "Default")
      (node (ref "DRIVER_IN1") (pin "5") (pinfunction "5_5") (pintype "passive"))
      (node (ref "R28") (pin "1") (pinfunction "1_1") (pintype "passive"))
    )
    (net (code "23") (name "Net-(DRIVER_IN1-Pad6)") (class "Default")
      (node (ref "DRIVER_IN1") (pin "6") (pinfunction "6_6") (pintype "passive"))
      (node (ref "R27") (pin "1") (pinfunction "1_1") (pintype "passive"))
    )
    (net (code "24") (name "Net-(DRIVER_IN1-Pad7)") (class "Default")
      (node (ref "DRIVER_IN1") (pin "7") (pinfunction "7_7") (pintype "passive"))
      (node (ref "R26") (pin "1") (pinfunction "1_1") (pintype "passive"))
    )
    (net (code "25") (name "Net-(DRIVER_IN1-Pad8)") (class "Default")
      (node (ref "DRIVER_IN1") (pin "8") (pinfunction "8_8") (pintype "passive"))
      (node (ref "R25") (pin "1") (pinfunction "1_1") (pintype "passive"))
    )
    (net (code "26") (name "Net-(DRIVER_IN1-Pad9)") (class "Default")
      (node (ref "DRIVER_IN1") (pin "9") (pinfunction "9_9") (pintype "passive"))
      (node (ref "R24") (pin "1") (pinfunction "1_1") (pintype "passive"))
    )
    (net (code "27") (name "Net-(DRIVER_IN1-Pad10)") (class "Default")
      (node (ref "DRIVER_IN1") (pin "10") (pinfunction "10_10") (pintype "passive"))
      (node (ref "R23") (pin "1") (pinfunction "1_1") (pintype "passive"))
    )
    (net (code "28") (name "Net-(DRIVER_IN1-Pad11)") (class "Default")
      (node (ref "DRIVER_IN1") (pin "11") (pinfunction "11_11") (pintype "passive"))
      (node (ref "R22") (pin "1") (pinfunction "1_1") (pintype "passive"))
    )
    (net (code "29") (name "Net-(DRIVER_IN1-Pad12)") (class "Default")
      (node (ref "DRIVER_IN1") (pin "12") (pinfunction "12_12") (pintype "passive"))
      (node (ref "R21") (pin "1") (pinfunction "1_1") (pintype "passive"))
    )
    (net (code "30") (name "Net-(DRIVER_IN1-Pad13)") (class "Default")
      (node (ref "DRIVER_IN1") (pin "13") (pinfunction "13_13") (pintype "passive"))
      (node (ref "R20") (pin "1") (pinfunction "1_1") (pintype "passive"))
    )
    (net (code "31") (name "Net-(DRIVER_IN1-Pad14)") (class "Default")
      (node (ref "DRIVER_IN1") (pin "14") (pinfunction "14_14") (pintype "passive"))
      (node (ref "R19") (pin "1") (pinfunction "1_1") (pintype "passive"))
    )
    (net (code "32") (name "Net-(DRIVER_IN1-Pad15)") (class "Default")
      (node (ref "DRIVER_IN1") (pin "15") (pinfunction "15_15") (pintype "passive"))
      (node (ref "R18") (pin "1") (pinfunction "1_1") (pintype "passive"))
    )
    (net (code "33") (name "Net-(DRIVER_IN1-Pad16)") (class "Default")
      (node (ref "DRIVER_IN1") (pin "16") (pinfunction "16_16") (pintype "passive"))
      (node (ref "R1") (pin "1") (pinfunction "1_1") (pintype "passive"))
    )
    (net (code "34") (name "Net-(DRIVER_IN2-Pad1)") (class "Default")
      (node (ref "DRIVER_IN2") (pin "1") (pinfunction "1_1") (pintype "passive"))
      (node (ref "R48") (pin "1") (pinfunction "1_1") (pintype "passive"))
    )
    (net (code "35") (name "Net-(DRIVER_IN2-Pad2)") (class "Default")
      (node (ref "DRIVER_IN2") (pin "2") (pinfunction "2_2") (pintype "passive"))
      (node (ref "R47") (pin "1") (pinfunction "1_1") (pintype "passive"))
    )
    (net (code "36") (name "Net-(DRIVER_IN2-Pad3)") (class "Default")
      (node (ref "DRIVER_IN2") (pin "3") (pinfunction "3_3") (pintype "passive"))
      (node (ref "R46") (pin "1") (pinfunction "1_1") (pintype "passive"))
    )
    (net (code "37") (name "Net-(DRIVER_IN2-Pad4)") (class "Default")
      (node (ref "DRIVER_IN2") (pin "4") (pinfunction "4_4") (pintype "passive"))
      (node (ref "R45") (pin "1") (pinfunction "1_1") (pintype "passive"))
    )
    (net (code "38") (name "Net-(DRIVER_IN2-Pad5)") (class "Default")
      (node (ref "DRIVER_IN2") (pin "5") (pinfunction "5_5") (pintype "passive"))
      (node (ref "R44") (pin "1") (pinfunction "1_1") (pintype "passive"))
    )
    (net (code "39") (name "Net-(DRIVER_IN2-Pad6)") (class "Default")
      (node (ref "DRIVER_IN2") (pin "6") (pinfunction "6_6") (pintype "passive"))
      (node (ref "R43") (pin "1") (pinfunction "1_1") (pintype "passive"))
    )
    (net (code "40") (name "Net-(DRIVER_IN2-Pad7)") (class "Default")
      (node (ref "DRIVER_IN2") (pin "7") (pinfunction "7_7") (pintype "passive"))
      (node (ref "R42") (pin "1") (pinfunction "1_1") (pintype "passive"))
    )
    (net (code "41") (name "Net-(DRIVER_IN2-Pad8)") (class "Default")
      (node (ref "DRIVER_IN2") (pin "8") (pinfunction "8_8") (pintype "passive"))
      (node (ref "R41") (pin "1") (pinfunction "1_1") (pintype "passive"))
    )
    (net (code "42") (name "Net-(DRIVER_IN2-Pad9)") (class "Default")
      (node (ref "DRIVER_IN2") (pin "9") (pinfunction "9_9") (pintype "passive"))
      (node (ref "R40") (pin "1") (pinfunction "1_1") (pintype "passive"))
    )
    (net (code "43") (name "Net-(DRIVER_IN2-Pad10)") (class "Default")
      (node (ref "DRIVER_IN2") (pin "10") (pinfunction "10_10") (pintype "passive"))
      (node (ref "R39") (pin "1") (pinfunction "1_1") (pintype "passive"))
    )
    (net (code "44") (name "Net-(DRIVER_IN2-Pad11)") (class "Default")
      (node (ref "DRIVER_IN2") (pin "11") (pinfunction "11_11") (pintype "passive"))
      (node (ref "R38") (pin "1") (pinfunction "1_1") (pintype "passive"))
    )
    (net (code "45") (name "Net-(DRIVER_IN2-Pad12)") (class "Default")
      (node (ref "DRIVER_IN2") (pin "12") (pinfunction "12_12") (pintype "passive"))
      (node (ref "R37") (pin "1") (pinfunction "1_1") (pintype "passive"))
    )
    (net (code "46") (name "Net-(DRIVER_IN2-Pad13)") (class "Default")
      (node (ref "DRIVER_IN2") (pin "13") (pinfunction "13_13") (pintype "passive"))
      (node (ref "R36") (pin "1") (pinfunction "1_1") (pintype "passive"))
    )
    (net (code "47") (name "Net-(DRIVER_IN2-Pad14)") (class "Default")
      (node (ref "DRIVER_IN2") (pin "14") (pinfunction "14_14") (pintype "passive"))
      (node (ref "R35") (pin "1") (pinfunction "1_1") (pintype "passive"))
    )
    (net (code "48") (name "Net-(DRIVER_IN2-Pad15)") (class "Default")
      (node (ref "DRIVER_IN2") (pin "15") (pinfunction "15_15") (pintype "passive"))
      (node (ref "R34") (pin "1") (pinfunction "1_1") (pintype "passive"))
    )
    (net (code "49") (name "Net-(DRIVER_IN2-Pad16)") (class "Default")
      (node (ref "DRIVER_IN2") (pin "16") (pinfunction "16_16") (pintype "passive"))
      (node (ref "R33") (pin "1") (pinfunction "1_1") (pintype "passive"))
    )
    (net (code "50") (name "Net-(DRIVER_IN3-Pad1)") (class "Default")
      (node (ref "DRIVER_IN3") (pin "1") (pinfunction "1_1") (pintype "passive"))
      (node (ref "R64") (pin "1") (pinfunction "1_1") (pintype "passive"))
    )
    (net (code "51") (name "Net-(DRIVER_IN3-Pad2)") (class "Default")
      (node (ref "DRIVER_IN3") (pin "2") (pinfunction "2_2") (pintype "passive"))
      (node (ref "R63") (pin "1") (pinfunction "1_1") (pintype "passive"))
    )
    (net (code "52") (name "Net-(DRIVER_IN3-Pad3)") (class "Default")
      (node (ref "DRIVER_IN3") (pin "3") (pinfunction "3_3") (pintype "passive"))
      (node (ref "R62") (pin "1") (pinfunction "1_1") (pintype "passive"))
    )
    (net (code "53") (name "Net-(DRIVER_IN3-Pad4)") (class "Default")
      (node (ref "DRIVER_IN3") (pin "4") (pinfunction "4_4") (pintype "passive"))
      (node (ref "R61") (pin "1") (pinfunction "1_1") (pintype "passive"))
    )
    (net (code "54") (name "Net-(DRIVER_IN3-Pad5)") (class "Default")
      (node (ref "DRIVER_IN3") (pin "5") (pinfunction "5_5") (pintype "passive"))
      (node (ref "R60") (pin "1") (pinfunction "1_1") (pintype "passive"))
    )
    (net (code "55") (name "Net-(DRIVER_IN3-Pad6)") (class "Default")
      (node (ref "DRIVER_IN3") (pin "6") (pinfunction "6_6") (pintype "passive"))
      (node (ref "R59") (pin "1") (pinfunction "1_1") (pintype "passive"))
    )
    (net (code "56") (name "Net-(DRIVER_IN3-Pad7)") (class "Default")
      (node (ref "DRIVER_IN3") (pin "7") (pinfunction "7_7") (pintype "passive"))
      (node (ref "R58") (pin "1") (pinfunction "1_1") (pintype "passive"))
    )
    (net (code "57") (name "Net-(DRIVER_IN3-Pad8)") (class "Default")
      (node (ref "DRIVER_IN3") (pin "8") (pinfunction "8_8") (pintype "passive"))
      (node (ref "R57") (pin "1") (pinfunction "1_1") (pintype "passive"))
    )
    (net (code "58") (name "Net-(DRIVER_IN3-Pad9)") (class "Default")
      (node (ref "DRIVER_IN3") (pin "9") (pinfunction "9_9") (pintype "passive"))
      (node (ref "R56") (pin "1") (pinfunction "1_1") (pintype "passive"))
    )
    (net (code "59") (name "Net-(DRIVER_IN3-Pad10)") (class "Default")
      (node (ref "DRIVER_IN3") (pin "10") (pinfunction "10_10") (pintype "passive"))
      (node (ref "R55") (pin "1") (pinfunction "1_1") (pintype "passive"))
    )
    (net (code "60") (name "Net-(DRIVER_IN3-Pad11)") (class "Default")
      (node (ref "DRIVER_IN3") (pin "11") (pinfunction "11_11") (pintype "passive"))
      (node (ref "R54") (pin "1") (pinfunction "1_1") (pintype "passive"))
    )
    (net (code "61") (name "Net-(DRIVER_IN3-Pad12)") (class "Default")
      (node (ref "DRIVER_IN3") (pin "12") (pinfunction "12_12") (pintype "passive"))
      (node (ref "R53") (pin "1") (pinfunction "1_1") (pintype "passive"))
    )
    (net (code "62") (name "Net-(DRIVER_IN3-Pad13)") (class "Default")
      (node (ref "DRIVER_IN3") (pin "13") (pinfunction "13_13") (pintype "passive"))
      (node (ref "R52") (pin "1") (pinfunction "1_1") (pintype "passive"))
    )
    (net (code "63") (name "Net-(DRIVER_IN3-Pad14)") (class "Default")
      (node (ref "DRIVER_IN3") (pin "14") (pinfunction "14_14") (pintype "passive"))
      (node (ref "R51") (pin "1") (pinfunction "1_1") (pintype "passive"))
    )
    (net (code "64") (name "Net-(DRIVER_IN3-Pad15)") (class "Default")
      (node (ref "DRIVER_IN3") (pin "15") (pinfunction "15_15") (pintype "passive"))
      (node (ref "R50") (pin "1") (pinfunction "1_1") (pintype "passive"))
    )
    (net (code "65") (name "Net-(DRIVER_IN3-Pad16)") (class "Default")
      (node (ref "DRIVER_IN3") (pin "16") (pinfunction "16_16") (pintype "passive"))
      (node (ref "R49") (pin "1") (pinfunction "1_1") (pintype "passive"))
    )
    (net (code "66") (name "Net-(FULL_SPECTRUM1A-S)") (class "Default")
      (node (ref "FULL_SPECTRUM") (pin "1") (pinfunction "S_1") (pintype "passive"))
      (node (ref "FULL_SPECTRUM1") (pin "1") (pinfunction "S_1") (pintype "passive"))
      (node (ref "FULL_SPECTRUM2") (pin "1") (pinfunction "S_1") (pintype "passive"))
      (node (ref "FULL_SPECTRUM3") (pin "1") (pinfunction "S_1") (pintype "passive"))
      (node (ref "GROUP_1") (pin "1") (pinfunction "S_1") (pintype "passive"))
      (node (ref "GROUP_10") (pin "1") (pinfunction "S_1") (pintype "passive"))
      (node (ref "GROUP_11") (pin "1") (pinfunction "S_1") (pintype "passive"))
      (node (ref "GROUP_12") (pin "1") (pinfunction "S_1") (pintype "passive"))
      (node (ref "GROUP_13") (pin "1") (pinfunction "S_1") (pintype "passive"))
      (node (ref "GROUP_14") (pin "1") (pinfunction "S_1") (pintype "passive"))
      (node (ref "GROUP_15") (pin "1") (pinfunction "S_1") (pintype "passive"))
      (node (ref "GROUP_16") (pin "1") (pinfunction "S_1") (pintype "passive"))
      (node (ref "GROUP_2") (pin "1") (pinfunction "S_1") (pintype "passive"))
      (node (ref "GROUP_3") (pin "1") (pinfunction "S_1") (pintype "passive"))
      (node (ref "GROUP_4") (pin "1") (pinfunction "S_1") (pintype "passive"))
      (node (ref "GROUP_5") (pin "1") (pinfunction "S_1") (pintype "passive"))
      (node (ref "GROUP_6") (pin "1") (pinfunction "S_1") (pintype "passive"))
      (node (ref "GROUP_7") (pin "1") (pinfunction "S_1") (pintype "passive"))
      (node (ref "GROUP_8") (pin "1") (pinfunction "S_1") (pintype "passive"))
      (node (ref "GROUP_9") (pin "1") (pinfunction "S_1") (pintype "passive"))
      (node (ref "J1") (pin "1") (pinfunction "S_1") (pintype "passive"))
      (node (ref "J11") (pin "1") (pinfunction "S_1") (pintype "passive"))
      (node (ref "J13") (pin "3") (pinfunction "3_3") (pintype "passive"))
      (node (ref "J2") (pin "1") (pinfunction "S_1") (pintype "passive"))
      (node (ref "J3") (pin "1") (pinfunction "S_1") (pintype "passive"))
      (node (ref "X1") (pin "1") (pinfunction "S_1") (pintype "passive"))
    )
    (net (code "67") (name "Net-(FULL_SPECTRUM1B-S)") (class "Default")
      (node (ref "FULL_SPECTRUM1") (pin "2") (pinfunction "S_2") (pintype "passive"))
      (node (ref "Q32") (pin "C") (pinfunction "C_C") (pintype "passive"))
    )
    (net (code "68") (name "Net-(FULL_SPECTRUM2B-S)") (class "Default")
      (node (ref "FULL_SPECTRUM2") (pin "2") (pinfunction "S_2") (pintype "passive"))
      (node (ref "Q48") (pin "C") (pinfunction "C_C") (pintype "passive"))
    )
    (net (code "69") (name "Net-(FULL_SPECTRUM3B-S)") (class "Default")
      (node (ref "FULL_SPECTRUM3") (pin "2") (pinfunction "S_2") (pintype "passive"))
      (node (ref "Q64") (pin "C") (pinfunction "C_C") (pintype "passive"))
    )
    (net (code "70") (name "Net-(FULL_SPECTRUMB-S)") (class "Default")
      (node (ref "FULL_SPECTRUM") (pin "2") (pinfunction "S_2") (pintype "passive"))
      (node (ref "Q16") (pin "C") (pinfunction "C_C") (pintype "passive"))
    )
    (net (code "71") (name "Net-(GROUP_1B-S)") (class "Default")
      (node (ref "GROUP_1") (pin "2") (pinfunction "S_2") (pintype "passive"))
      (node (ref "Q1") (pin "C") (pinfunction "C_C") (pintype "passive"))
    )
    (net (code "72") (name "Net-(GROUP_1C-S)") (class "Default")
      (node (ref "GROUP_1") (pin "3") (pinfunction "S_3") (pintype "passive"))
      (node (ref "Q2") (pin "C") (pinfunction "C_C") (pintype "passive"))
    )
    (net (code "73") (name "Net-(GROUP_1D-S)") (class "Default")
      (node (ref "GROUP_1") (pin "4") (pinfunction "S_4") (pintype "passive"))
      (node (ref "Q3") (pin "C") (pinfunction "C_C") (pintype "passive"))
    )
    (net (code "74") (name "Net-(GROUP_2B-S)") (class "Default")
      (node (ref "GROUP_2") (pin "2") (pinfunction "S_2") (pintype "passive"))
      (node (ref "Q4") (pin "C") (pinfunction "C_C") (pintype "passive"))
    )
    (net (code "75") (name "Net-(GROUP_2C-S)") (class "Default")
      (node (ref "GROUP_2") (pin "3") (pinfunction "S_3") (pintype "passive"))
      (node (ref "Q5") (pin "C") (pinfunction "C_C") (pintype "passive"))
    )
    (net (code "76") (name "Net-(GROUP_2D-S)") (class "Default")
      (node (ref "GROUP_2") (pin "4") (pinfunction "S_4") (pintype "passive"))
      (node (ref "Q6") (pin "C") (pinfunction "C_C") (pintype "passive"))
    )
    (net (code "77") (name "Net-(GROUP_3B-S)") (class "Default")
      (node (ref "GROUP_3") (pin "2") (pinfunction "S_2") (pintype "passive"))
      (node (ref "Q7") (pin "C") (pinfunction "C_C") (pintype "passive"))
    )
    (net (code "78") (name "Net-(GROUP_3C-S)") (class "Default")
      (node (ref "GROUP_3") (pin "3") (pinfunction "S_3") (pintype "passive"))
      (node (ref "Q8") (pin "C") (pinfunction "C_C") (pintype "passive"))
    )
    (net (code "79") (name "Net-(GROUP_3D-S)") (class "Default")
      (node (ref "GROUP_3") (pin "4") (pinfunction "S_4") (pintype "passive"))
      (node (ref "Q9") (pin "C") (pinfunction "C_C") (pintype "passive"))
    )
    (net (code "80") (name "Net-(GROUP_4B-S)") (class "Default")
      (node (ref "GROUP_4") (pin "2") (pinfunction "S_2") (pintype "passive"))
      (node (ref "Q10") (pin "C") (pinfunction "C_C") (pintype "passive"))
    )
    (net (code "81") (name "Net-(GROUP_4C-S)") (class "Default")
      (node (ref "GROUP_4") (pin "3") (pinfunction "S_3") (pintype "passive"))
      (node (ref "Q11") (pin "C") (pinfunction "C_C") (pintype "passive"))
    )
    (net (code "82") (name "Net-(GROUP_4D-S)") (class "Default")
      (node (ref "GROUP_4") (pin "4") (pinfunction "S_4") (pintype "passive"))
      (node (ref "Q12") (pin "C") (pinfunction "C_C") (pintype "passive"))
    )
    (net (code "83") (name "Net-(GROUP_5B-S)") (class "Default")
      (node (ref "GROUP_5") (pin "2") (pinfunction "S_2") (pintype "passive"))
      (node (ref "Q17") (pin "C") (pinfunction "C_C") (pintype "passive"))
    )
    (net (code "84") (name "Net-(GROUP_5C-S)") (class "Default")
      (node (ref "GROUP_5") (pin "3") (pinfunction "S_3") (pintype "passive"))
      (node (ref "Q18") (pin "C") (pinfunction "C_C") (pintype "passive"))
    )
    (net (code "85") (name "Net-(GROUP_5D-S)") (class "Default")
      (node (ref "GROUP_5") (pin "4") (pinfunction "S_4") (pintype "passive"))
      (node (ref "Q19") (pin "C") (pinfunction "C_C") (pintype "passive"))
    )
    (net (code "86") (name "Net-(GROUP_6B-S)") (class "Default")
      (node (ref "GROUP_6") (pin "2") (pinfunction "S_2") (pintype "passive"))
      (node (ref "Q20") (pin "C") (pinfunction "C_C") (pintype "passive"))
    )
    (net (code "87") (name "Net-(GROUP_6C-S)") (class "Default")
      (node (ref "GROUP_6") (pin "3") (pinfunction "S_3") (pintype "passive"))
      (node (ref "Q21") (pin "C") (pinfunction "C_C") (pintype "passive"))
    )
    (net (code "88") (name "Net-(GROUP_6D-S)") (class "Default")
      (node (ref "GROUP_6") (pin "4") (pinfunction "S_4") (pintype "passive"))
      (node (ref "Q22") (pin "C") (pinfunction "C_C") (pintype "passive"))
    )
    (net (code "89") (name "Net-(GROUP_7B-S)") (class "Default")
      (node (ref "GROUP_7") (pin "2") (pinfunction "S_2") (pintype "passive"))
      (node (ref "Q23") (pin "C") (pinfunction "C_C") (pintype "passive"))
    )
    (net (code "90") (name "Net-(GROUP_7C-S)") (class "Default")
      (node (ref "GROUP_7") (pin "3") (pinfunction "S_3") (pintype "passive"))
      (node (ref "Q24") (pin "C") (pinfunction "C_C") (pintype "passive"))
    )
    (net (code "91") (name "Net-(GROUP_7D-S)") (class "Default")
      (node (ref "GROUP_7") (pin "4") (pinfunction "S_4") (pintype "passive"))
      (node (ref "Q25") (pin "C") (pinfunction "C_C") (pintype "passive"))
    )
    (net (code "92") (name "Net-(GROUP_8B-S)") (class "Default")
      (node (ref "GROUP_8") (pin "2") (pinfunction "S_2") (pintype "passive"))
      (node (ref "Q26") (pin "C") (pinfunction "C_C") (pintype "passive"))
    )
    (net (code "93") (name "Net-(GROUP_8C-S)") (class "Default")
      (node (ref "GROUP_8") (pin "3") (pinfunction "S_3") (pintype "passive"))
      (node (ref "Q27") (pin "C") (pinfunction "C_C") (pintype "passive"))
    )
    (net (code "94") (name "Net-(GROUP_8D-S)") (class "Default")
      (node (ref "GROUP_8") (pin "4") (pinfunction "S_4") (pintype "passive"))
      (node (ref "Q28") (pin "C") (pinfunction "C_C") (pintype "passive"))
    )
    (net (code "95") (name "Net-(GROUP_9B-S)") (class "Default")
      (node (ref "GROUP_9") (pin "2") (pinfunction "S_2") (pintype "passive"))
      (node (ref "Q33") (pin "C") (pinfunction "C_C") (pintype "passive"))
    )
    (net (code "96") (name "Net-(GROUP_9C-S)") (class "Default")
      (node (ref "GROUP_9") (pin "3") (pinfunction "S_3") (pintype "passive"))
      (node (ref "Q34") (pin "C") (pinfunction "C_C") (pintype "passive"))
    )
    (net (code "97") (name "Net-(GROUP_9D-S)") (class "Default")
      (node (ref "GROUP_9") (pin "4") (pinfunction "S_4") (pintype "passive"))
      (node (ref "Q35") (pin "C") (pinfunction "C_C") (pintype "passive"))
    )
    (net (code "98") (name "Net-(GROUP_10B-S)") (class "Default")
      (node (ref "GROUP_10") (pin "2") (pinfunction "S_2") (pintype "passive"))
      (node (ref "Q36") (pin "C") (pinfunction "C_C") (pintype "passive"))
    )
    (net (code "99") (name "Net-(GROUP_10C-S)") (class "Default")
      (node (ref "GROUP_10") (pin "3") (pinfunction "S_3") (pintype "passive"))
      (node (ref "Q37") (pin "C") (pinfunction "C_C") (pintype "passive"))
    )
    (net (code "100") (name "Net-(GROUP_10D-S)") (class "Default")
      (node (ref "GROUP_10") (pin "4") (pinfunction "S_4") (pintype "passive"))
      (node (ref "Q38") (pin "C") (pinfunction "C_C") (pintype "passive"))
    )
    (net (code "101") (name "Net-(GROUP_11B-S)") (class "Default")
      (node (ref "GROUP_11") (pin "2") (pinfunction "S_2") (pintype "passive"))
      (node (ref "Q39") (pin "C") (pinfunction "C_C") (pintype "passive"))
    )
    (net (code "102") (name "Net-(GROUP_11C-S)") (class "Default")
      (node (ref "GROUP_11") (pin "3") (pinfunction "S_3") (pintype "passive"))
      (node (ref "Q40") (pin "C") (pinfunction "C_C") (pintype "passive"))
    )
    (net (code "103") (name "Net-(GROUP_11D-S)") (class "Default")
      (node (ref "GROUP_11") (pin "4") (pinfunction "S_4") (pintype "passive"))
      (node (ref "Q41") (pin "C") (pinfunction "C_C") (pintype "passive"))
    )
    (net (code "104") (name "Net-(GROUP_12B-S)") (class "Default")
      (node (ref "GROUP_12") (pin "2") (pinfunction "S_2") (pintype "passive"))
      (node (ref "Q42") (pin "C") (pinfunction "C_C") (pintype "passive"))
    )
    (net (code "105") (name "Net-(GROUP_12C-S)") (class "Default")
      (node (ref "GROUP_12") (pin "3") (pinfunction "S_3") (pintype "passive"))
      (node (ref "Q43") (pin "C") (pinfunction "C_C") (pintype "passive"))
    )
    (net (code "106") (name "Net-(GROUP_12D-S)") (class "Default")
      (node (ref "GROUP_12") (pin "4") (pinfunction "S_4") (pintype "passive"))
      (node (ref "Q44") (pin "C") (pinfunction "C_C") (pintype "passive"))
    )
    (net (code "107") (name "Net-(GROUP_13B-S)") (class "Default")
      (node (ref "GROUP_13") (pin "2") (pinfunction "S_2") (pintype "passive"))
      (node (ref "Q49") (pin "C") (pinfunction "C_C") (pintype "passive"))
    )
    (net (code "108") (name "Net-(GROUP_13C-S)") (class "Default")
      (node (ref "GROUP_13") (pin "3") (pinfunction "S_3") (pintype "passive"))
      (node (ref "Q50") (pin "C") (pinfunction "C_C") (pintype "passive"))
    )
    (net (code "109") (name "Net-(GROUP_13D-S)") (class "Default")
      (node (ref "GROUP_13") (pin "4") (pinfunction "S_4") (pintype "passive"))
      (node (ref "Q51") (pin "C") (pinfunction "C_C") (pintype "passive"))
    )
    (net (code "110") (name "Net-(GROUP_14B-S)") (class "Default")
      (node (ref "GROUP_14") (pin "2") (pinfunction "S_2") (pintype "passive"))
      (node (ref "Q52") (pin "C") (pinfunction "C_C") (pintype "passive"))
    )
    (net (code "111") (name "Net-(GROUP_14C-S)") (class "Default")
      (node (ref "GROUP_14") (pin "3") (pinfunction "S_3") (pintype "passive"))
      (node (ref "Q53") (pin "C") (pinfunction "C_C") (pintype "passive"))
    )
    (net (code "112") (name "Net-(GROUP_14D-S)") (class "Default")
      (node (ref "GROUP_14") (pin "4") (pinfunction "S_4") (pintype "passive"))
      (node (ref "Q54") (pin "C") (pinfunction "C_C") (pintype "passive"))
    )
    (net (code "113") (name "Net-(GROUP_15B-S)") (class "Default")
      (node (ref "GROUP_15") (pin "2") (pinfunction "S_2") (pintype "passive"))
      (node (ref "Q55") (pin "C") (pinfunction "C_C") (pintype "passive"))
    )
    (net (code "114") (name "Net-(GROUP_15C-S)") (class "Default")
      (node (ref "GROUP_15") (pin "3") (pinfunction "S_3") (pintype "passive"))
      (node (ref "Q56") (pin "C") (pinfunction "C_C") (pintype "passive"))
    )
    (net (code "115") (name "Net-(GROUP_15D-S)") (class "Default")
      (node (ref "GROUP_15") (pin "4") (pinfunction "S_4") (pintype "passive"))
      (node (ref "Q57") (pin "C") (pinfunction "C_C") (pintype "passive"))
    )
    (net (code "116") (name "Net-(GROUP_16B-S)") (class "Default")
      (node (ref "GROUP_16") (pin "2") (pinfunction "S_2") (pintype "passive"))
      (node (ref "Q58") (pin "C") (pinfunction "C_C") (pintype "passive"))
    )
    (net (code "117") (name "Net-(GROUP_16C-S)") (class "Default")
      (node (ref "GROUP_16") (pin "3") (pinfunction "S_3") (pintype "passive"))
      (node (ref "Q59") (pin "C") (pinfunction "C_C") (pintype "passive"))
    )
    (net (code "118") (name "Net-(GROUP_16D-S)") (class "Default")
      (node (ref "GROUP_16") (pin "4") (pinfunction "S_4") (pintype "passive"))
      (node (ref "Q60") (pin "C") (pinfunction "C_C") (pintype "passive"))
    )
    (net (code "119") (name "Net-(J1B-S)") (class "Default")
      (node (ref "J1") (pin "2") (pinfunction "S_2") (pintype "passive"))
      (node (ref "Q29") (pin "C") (pinfunction "C_C") (pintype "passive"))
    )
    (net (code "120") (name "Net-(J1C-S)") (class "Default")
      (node (ref "J1") (pin "3") (pinfunction "S_3") (pintype "passive"))
      (node (ref "Q30") (pin "C") (pinfunction "C_C") (pintype "passive"))
    )
    (net (code "121") (name "Net-(J1D-S)") (class "Default")
      (node (ref "J1") (pin "4") (pinfunction "S_4") (pintype "passive"))
      (node (ref "Q31") (pin "C") (pinfunction "C_C") (pintype "passive"))
    )
    (net (code "122") (name "Net-(J2B-S)") (class "Default")
      (node (ref "J2") (pin "2") (pinfunction "S_2") (pintype "passive"))
      (node (ref "Q45") (pin "C") (pinfunction "C_C") (pintype "passive"))
    )
    (net (code "123") (name "Net-(J2C-S)") (class "Default")
      (node (ref "J2") (pin "3") (pinfunction "S_3") (pintype "passive"))
      (node (ref "Q46") (pin "C") (pinfunction "C_C") (pintype "passive"))
    )
    (net (code "124") (name "Net-(J2D-S)") (class "Default")
      (node (ref "J2") (pin "4") (pinfunction "S_4") (pintype "passive"))
      (node (ref "Q47") (pin "C") (pinfunction "C_C") (pintype "passive"))
    )
    (net (code "125") (name "Net-(J3B-S)") (class "Default")
      (node (ref "J3") (pin "2") (pinfunction "S_2") (pintype "passive"))
      (node (ref "Q61") (pin "C") (pinfunction "C_C") (pintype "passive"))
    )
    (net (code "126") (name "Net-(J3C-S)") (class "Default")
      (node (ref "J3") (pin "3") (pinfunction "S_3") (pintype "passive"))
      (node (ref "Q62") (pin "C") (pinfunction "C_C") (pintype "passive"))
    )
    (net (code "127") (name "Net-(J3D-S)") (class "Default")
      (node (ref "J3") (pin "4") (pinfunction "S_4") (pintype "passive"))
      (node (ref "Q63") (pin "C") (pinfunction "C_C") (pintype "passive"))
    )
    (net (code "128") (name "Net-(J11B-S)") (class "Default")
      (node (ref "J11") (pin "2") (pinfunction "S_2") (pintype "passive"))
      (node (ref "Q13") (pin "C") (pinfunction "C_C") (pintype "passive"))
    )
    (net (code "129") (name "Net-(J11C-S)") (class "Default")
      (node (ref "J11") (pin "3") (pinfunction "S_3") (pintype "passive"))
      (node (ref "Q14") (pin "C") (pinfunction "C_C") (pintype "passive"))
    )
    (net (code "130") (name "Net-(J11D-S)") (class "Default")
      (node (ref "J11") (pin "4") (pinfunction "S_4") (pintype "passive"))
      (node (ref "Q15") (pin "C") (pinfunction "C_C") (pintype "passive"))
    )
    (net (code "131") (name "Net-(Q1-PadB)") (class "Default")
      (node (ref "Q1") (pin "B") (pinfunction "B_B") (pintype "passive"))
      (node (ref "R2") (pin "2") (pinfunction "2_2") (pintype "passive"))
    )
    (net (code "132") (name "Net-(Q2-PadB)") (class "Default")
      (node (ref "Q2") (pin "B") (pinfunction "B_B") (pintype "passive"))
      (node (ref "R3") (pin "2") (pinfunction "2_2") (pintype "passive"))
    )
    (net (code "133") (name "Net-(Q3-PadB)") (class "Default")
      (node (ref "Q3") (pin "B") (pinfunction "B_B") (pintype "passive"))
      (node (ref "R4") (pin "2") (pinfunction "2_2") (pintype "passive"))
    )
    (net (code "134") (name "Net-(Q4-PadB)") (class "Default")
      (node (ref "Q4") (pin "B") (pinfunction "B_B") (pintype "passive"))
      (node (ref "R5") (pin "2") (pinfunction "2_2") (pintype "passive"))
    )
    (net (code "135") (name "Net-(Q5-PadB)") (class "Default")
      (node (ref "Q5") (pin "B") (pinfunction "B_B") (pintype "passive"))
      (node (ref "R6") (pin "2") (pinfunction "2_2") (pintype "passive"))
    )
    (net (code "136") (name "Net-(Q6-PadB)") (class "Default")
      (node (ref "Q6") (pin "B") (pinfunction "B_B") (pintype "passive"))
      (node (ref "R7") (pin "2") (pinfunction "2_2") (pintype "passive"))
    )
    (net (code "137") (name "Net-(Q7-PadB)") (class "Default")
      (node (ref "Q7") (pin "B") (pinfunction "B_B") (pintype "passive"))
      (node (ref "R8") (pin "2") (pinfunction "2_2") (pintype "passive"))
    )
    (net (code "138") (name "Net-(Q8-PadB)") (class "Default")
      (node (ref "Q8") (pin "B") (pinfunction "B_B") (pintype "passive"))
      (node (ref "R9") (pin "2") (pinfunction "2_2") (pintype "passive"))
    )
    (net (code "139") (name "Net-(Q9-PadB)") (class "Default")
      (node (ref "Q9") (pin "B") (pinfunction "B_B") (pintype "passive"))
      (node (ref "R10") (pin "2") (pinfunction "2_2") (pintype "passive"))
    )
    (net (code "140") (name "Net-(Q10-PadB)") (class "Default")
      (node (ref "Q10") (pin "B") (pinfunction "B_B") (pintype "passive"))
      (node (ref "R11") (pin "2") (pinfunction "2_2") (pintype "passive"))
    )
    (net (code "141") (name "Net-(Q11-PadB)") (class "Default")
      (node (ref "Q11") (pin "B") (pinfunction "B_B") (pintype "passive"))
      (node (ref "R12") (pin "2") (pinfunction "2_2") (pintype "passive"))
    )
    (net (code "142") (name "Net-(Q12-PadB)") (class "Default")
      (node (ref "Q12") (pin "B") (pinfunction "B_B") (pintype "passive"))
      (node (ref "R13") (pin "2") (pinfunction "2_2") (pintype "passive"))
    )
    (net (code "143") (name "Net-(Q13-PadB)") (class "Default")
      (node (ref "Q13") (pin "B") (pinfunction "B_B") (pintype "passive"))
      (node (ref "R14") (pin "2") (pinfunction "2_2") (pintype "passive"))
    )
    (net (code "144") (name "Net-(Q14-PadB)") (class "Default")
      (node (ref "Q14") (pin "B") (pinfunction "B_B") (pintype "passive"))
      (node (ref "R15") (pin "2") (pinfunction "2_2") (pintype "passive"))
    )
    (net (code "145") (name "Net-(Q15-PadB)") (class "Default")
      (node (ref "Q15") (pin "B") (pinfunction "B_B") (pintype "passive"))
      (node (ref "R16") (pin "2") (pinfunction "2_2") (pintype "passive"))
    )
    (net (code "146") (name "Net-(Q16-PadB)") (class "Default")
      (node (ref "Q16") (pin "B") (pinfunction "B_B") (pintype "passive"))
      (node (ref "R17") (pin "2") (pinfunction "2_2") (pintype "passive"))
    )
    (net (code "147") (name "Net-(Q17-PadB)") (class "Default")
      (node (ref "Q17") (pin "B") (pinfunction "B_B") (pintype "passive"))
      (node (ref "R1") (pin "2") (pinfunction "2_2") (pintype "passive"))
    )
    (net (code "148") (name "Net-(Q18-PadB)") (class "Default")
      (node (ref "Q18") (pin "B") (pinfunction "B_B") (pintype "passive"))
      (node (ref "R18") (pin "2") (pinfunction "2_2") (pintype "passive"))
    )
    (net (code "149") (name "Net-(Q19-PadB)") (class "Default")
      (node (ref "Q19") (pin "B") (pinfunction "B_B") (pintype "passive"))
      (node (ref "R19") (pin "2") (pinfunction "2_2") (pintype "passive"))
    )
    (net (code "150") (name "Net-(Q20-PadB)") (class "Default")
      (node (ref "Q20") (pin "B") (pinfunction "B_B") (pintype "passive"))
      (node (ref "R20") (pin "2") (pinfunction "2_2") (pintype "passive"))
    )
    (net (code "151") (name "Net-(Q21-PadB)") (class "Default")
      (node (ref "Q21") (pin "B") (pinfunction "B_B") (pintype "passive"))
      (node (ref "R21") (pin "2") (pinfunction "2_2") (pintype "passive"))
    )
    (net (code "152") (name "Net-(Q22-PadB)") (class "Default")
      (node (ref "Q22") (pin "B") (pinfunction "B_B") (pintype "passive"))
      (node (ref "R22") (pin "2") (pinfunction "2_2") (pintype "passive"))
    )
    (net (code "153") (name "Net-(Q23-PadB)") (class "Default")
      (node (ref "Q23") (pin "B") (pinfunction "B_B") (pintype "passive"))
      (node (ref "R23") (pin "2") (pinfunction "2_2") (pintype "passive"))
    )
    (net (code "154") (name "Net-(Q24-PadB)") (class "Default")
      (node (ref "Q24") (pin "B") (pinfunction "B_B") (pintype "passive"))
      (node (ref "R24") (pin "2") (pinfunction "2_2") (pintype "passive"))
    )
    (net (code "155") (name "Net-(Q25-PadB)") (class "Default")
      (node (ref "Q25") (pin "B") (pinfunction "B_B") (pintype "passive"))
      (node (ref "R25") (pin "2") (pinfunction "2_2") (pintype "passive"))
    )
    (net (code "156") (name "Net-(Q26-PadB)") (class "Default")
      (node (ref "Q26") (pin "B") (pinfunction "B_B") (pintype "passive"))
      (node (ref "R26") (pin "2") (pinfunction "2_2") (pintype "passive"))
    )
    (net (code "157") (name "Net-(Q27-PadB)") (class "Default")
      (node (ref "Q27") (pin "B") (pinfunction "B_B") (pintype "passive"))
      (node (ref "R27") (pin "2") (pinfunction "2_2") (pintype "passive"))
    )
    (net (code "158") (name "Net-(Q28-PadB)") (class "Default")
      (node (ref "Q28") (pin "B") (pinfunction "B_B") (pintype "passive"))
      (node (ref "R28") (pin "2") (pinfunction "2_2") (pintype "passive"))
    )
    (net (code "159") (name "Net-(Q29-PadB)") (class "Default")
      (node (ref "Q29") (pin "B") (pinfunction "B_B") (pintype "passive"))
      (node (ref "R29") (pin "2") (pinfunction "2_2") (pintype "passive"))
    )
    (net (code "160") (name "Net-(Q30-PadB)") (class "Default")
      (node (ref "Q30") (pin "B") (pinfunction "B_B") (pintype "passive"))
      (node (ref "R30") (pin "2") (pinfunction "2_2") (pintype "passive"))
    )
    (net (code "161") (name "Net-(Q31-PadB)") (class "Default")
      (node (ref "Q31") (pin "B") (pinfunction "B_B") (pintype "passive"))
      (node (ref "R31") (pin "2") (pinfunction "2_2") (pintype "passive"))
    )
    (net (code "162") (name "Net-(Q32-PadB)") (class "Default")
      (node (ref "Q32") (pin "B") (pinfunction "B_B") (pintype "passive"))
      (node (ref "R32") (pin "2") (pinfunction "2_2") (pintype "passive"))
    )
    (net (code "163") (name "Net-(Q33-PadB)") (class "Default")
      (node (ref "Q33") (pin "B") (pinfunction "B_B") (pintype "passive"))
      (node (ref "R33") (pin "2") (pinfunction "2_2") (pintype "passive"))
    )
    (net (code "164") (name "Net-(Q34-PadB)") (class "Default")
      (node (ref "Q34") (pin "B") (pinfunction "B_B") (pintype "passive"))
      (node (ref "R34") (pin "2") (pinfunction "2_2") (pintype "passive"))
    )
    (net (code "165") (name "Net-(Q35-PadB)") (class "Default")
      (node (ref "Q35") (pin "B") (pinfunction "B_B") (pintype "passive"))
      (node (ref "R35") (pin "2") (pinfunction "2_2") (pintype "passive"))
    )
    (net (code "166") (name "Net-(Q36-PadB)") (class "Default")
      (node (ref "Q36") (pin "B") (pinfunction "B_B") (pintype "passive"))
      (node (ref "R36") (pin "2") (pinfunction "2_2") (pintype "passive"))
    )
    (net (code "167") (name "Net-(Q37-PadB)") (class "Default")
      (node (ref "Q37") (pin "B") (pinfunction "B_B") (pintype "passive"))
      (node (ref "R37") (pin "2") (pinfunction "2_2") (pintype "passive"))
    )
    (net (code "168") (name "Net-(Q38-PadB)") (class "Default")
      (node (ref "Q38") (pin "B") (pinfunction "B_B") (pintype "passive"))
      (node (ref "R38") (pin "2") (pinfunction "2_2") (pintype "passive"))
    )
    (net (code "169") (name "Net-(Q39-PadB)") (class "Default")
      (node (ref "Q39") (pin "B") (pinfunction "B_B") (pintype "passive"))
      (node (ref "R39") (pin "2") (pinfunction "2_2") (pintype "passive"))
    )
    (net (code "170") (name "Net-(Q40-PadB)") (class "Default")
      (node (ref "Q40") (pin "B") (pinfunction "B_B") (pintype "passive"))
      (node (ref "R40") (pin "2") (pinfunction "2_2") (pintype "passive"))
    )
    (net (code "171") (name "Net-(Q41-PadB)") (class "Default")
      (node (ref "Q41") (pin "B") (pinfunction "B_B") (pintype "passive"))
      (node (ref "R41") (pin "2") (pinfunction "2_2") (pintype "passive"))
    )
    (net (code "172") (name "Net-(Q42-PadB)") (class "Default")
      (node (ref "Q42") (pin "B") (pinfunction "B_B") (pintype "passive"))
      (node (ref "R42") (pin "2") (pinfunction "2_2") (pintype "passive"))
    )
    (net (code "173") (name "Net-(Q43-PadB)") (class "Default")
      (node (ref "Q43") (pin "B") (pinfunction "B_B") (pintype "passive"))
      (node (ref "R43") (pin "2") (pinfunction "2_2") (pintype "passive"))
    )
    (net (code "174") (name "Net-(Q44-PadB)") (class "Default")
      (node (ref "Q44") (pin "B") (pinfunction "B_B") (pintype "passive"))
      (node (ref "R44") (pin "2") (pinfunction "2_2") (pintype "passive"))
    )
    (net (code "175") (name "Net-(Q45-PadB)") (class "Default")
      (node (ref "Q45") (pin "B") (pinfunction "B_B") (pintype "passive"))
      (node (ref "R45") (pin "2") (pinfunction "2_2") (pintype "passive"))
    )
    (net (code "176") (name "Net-(Q46-PadB)") (class "Default")
      (node (ref "Q46") (pin "B") (pinfunction "B_B") (pintype "passive"))
      (node (ref "R46") (pin "2") (pinfunction "2_2") (pintype "passive"))
    )
    (net (code "177") (name "Net-(Q47-PadB)") (class "Default")
      (node (ref "Q47") (pin "B") (pinfunction "B_B") (pintype "passive"))
      (node (ref "R47") (pin "2") (pinfunction "2_2") (pintype "passive"))
    )
    (net (code "178") (name "Net-(Q48-PadB)") (class "Default")
      (node (ref "Q48") (pin "B") (pinfunction "B_B") (pintype "passive"))
      (node (ref "R48") (pin "2") (pinfunction "2_2") (pintype "passive"))
    )
    (net (code "179") (name "Net-(Q49-PadB)") (class "Default")
      (node (ref "Q49") (pin "B") (pinfunction "B_B") (pintype "passive"))
      (node (ref "R49") (pin "2") (pinfunction "2_2") (pintype "passive"))
    )
    (net (code "180") (name "Net-(Q50-PadB)") (class "Default")
      (node (ref "Q50") (pin "B") (pinfunction "B_B") (pintype "passive"))
      (node (ref "R50") (pin "2") (pinfunction "2_2") (pintype "passive"))
    )
    (net (code "181") (name "Net-(Q51-PadB)") (class "Default")
      (node (ref "Q51") (pin "B") (pinfunction "B_B") (pintype "passive"))
      (node (ref "R51") (pin "2") (pinfunction "2_2") (pintype "passive"))
    )
    (net (code "182") (name "Net-(Q52-PadB)") (class "Default")
      (node (ref "Q52") (pin "B") (pinfunction "B_B") (pintype "passive"))
      (node (ref "R52") (pin "2") (pinfunction "2_2") (pintype "passive"))
    )
    (net (code "183") (name "Net-(Q53-PadB)") (class "Default")
      (node (ref "Q53") (pin "B") (pinfunction "B_B") (pintype "passive"))
      (node (ref "R53") (pin "2") (pinfunction "2_2") (pintype "passive"))
    )
    (net (code "184") (name "Net-(Q54-PadB)") (class "Default")
      (node (ref "Q54") (pin "B") (pinfunction "B_B") (pintype "passive"))
      (node (ref "R54") (pin "2") (pinfunction "2_2") (pintype "passive"))
    )
    (net (code "185") (name "Net-(Q55-PadB)") (class "Default")
      (node (ref "Q55") (pin "B") (pinfunction "B_B") (pintype "passive"))
      (node (ref "R55") (pin "2") (pinfunction "2_2") (pintype "passive"))
    )
    (net (code "186") (name "Net-(Q56-PadB)") (class "Default")
      (node (ref "Q56") (pin "B") (pinfunction "B_B") (pintype "passive"))
      (node (ref "R56") (pin "2") (pinfunction "2_2") (pintype "passive"))
    )
    (net (code "187") (name "Net-(Q57-PadB)") (class "Default")
      (node (ref "Q57") (pin "B") (pinfunction "B_B") (pintype "passive"))
      (node (ref "R57") (pin "2") (pinfunction "2_2") (pintype "passive"))
    )
    (net (code "188") (name "Net-(Q58-PadB)") (class "Default")
      (node (ref "Q58") (pin "B") (pinfunction "B_B") (pintype "passive"))
      (node (ref "R58") (pin "2") (pinfunction "2_2") (pintype "passive"))
    )
    (net (code "189") (name "Net-(Q59-PadB)") (class "Default")
      (node (ref "Q59") (pin "B") (pinfunction "B_B") (pintype "passive"))
      (node (ref "R59") (pin "2") (pinfunction "2_2") (pintype "passive"))
    )
    (net (code "190") (name "Net-(Q60-PadB)") (class "Default")
      (node (ref "Q60") (pin "B") (pinfunction "B_B") (pintype "passive"))
      (node (ref "R60") (pin "2") (pinfunction "2_2") (pintype "passive"))
    )
    (net (code "191") (name "Net-(Q61-PadB)") (class "Default")
      (node (ref "Q61") (pin "B") (pinfunction "B_B") (pintype "passive"))
      (node (ref "R61") (pin "2") (pinfunction "2_2") (pintype "passive"))
    )
    (net (code "192") (name "Net-(Q62-PadB)") (class "Default")
      (node (ref "Q62") (pin "B") (pinfunction "B_B") (pintype "passive"))
      (node (ref "R62") (pin "2") (pinfunction "2_2") (pintype "passive"))
    )
    (net (code "193") (name "Net-(Q63-PadB)") (class "Default")
      (node (ref "Q63") (pin "B") (pinfunction "B_B") (pintype "passive"))
      (node (ref "R63") (pin "2") (pinfunction "2_2") (pintype "passive"))
    )
    (net (code "194") (name "Net-(Q64-PadB)") (class "Default")
      (node (ref "Q64") (pin "B") (pinfunction "B_B") (pintype "passive"))
      (node (ref "R64") (pin "2") (pinfunction "2_2") (pintype "passive"))
    )
    (net (code "195") (name "Net-(U$1-IO2)") (class "Default")
      (node (ref "RELAY_BAR") (pin "8") (pinfunction "8_8") (pintype "passive"))
      (node (ref "U$1") (pin "4") (pinfunction "IO2_4") (pintype "bidirectional"))
    )
    (net (code "196") (name "Net-(U$1-IO4)") (class "Default")
      (node (ref "RELAY_BAR") (pin "7") (pinfunction "7_7") (pintype "passive"))
      (node (ref "U$1") (pin "5") (pinfunction "IO4_5") (pintype "bidirectional"))
    )
    (net (code "197") (name "Net-(U$1-IO5)") (class "Default")
      (node (ref "RELAY_BAR") (pin "4") (pinfunction "4_4") (pintype "passive"))
      (node (ref "U$1") (pin "8") (pinfunction "IO5_8") (pintype "bidirectional"))
    )
    (net (code "198") (name "Net-(U$1-IO15)") (class "Default")
      (node (ref "RELAY_BAR") (pin "9") (pinfunction "9_9") (pintype "passive"))
      (node (ref "U$1") (pin "3") (pinfunction "IO15_3") (pintype "bidirectional"))
    )
    (net (code "199") (name "Net-(U$1-IO16)") (class "Default")
      (node (ref "RELAY_BAR") (pin "6") (pinfunction "6_6") (pintype "passive"))
      (node (ref "U$1") (pin "6") (pinfunction "IO16_6") (pintype "bidirectional"))
    )
    (net (code "200") (name "Net-(U$1-IO17)") (class "Default")
      (node (ref "RELAY_BAR") (pin "5") (pinfunction "5_5") (pintype "passive"))
      (node (ref "U$1") (pin "7") (pinfunction "IO17_7") (pintype "bidirectional"))
    )
    (net (code "201") (name "Net-(U$1-IO18)") (class "Default")
      (node (ref "RELAY_BAR") (pin "3") (pinfunction "3_3") (pintype "passive"))
      (node (ref "U$1") (pin "9") (pinfunction "IO18_9") (pintype "bidirectional"))
    )
    (net (code "202") (name "Net-(U$1-IO19)") (class "Default")
      (node (ref "RELAY_BAR") (pin "2") (pinfunction "2_2") (pintype "passive"))
      (node (ref "U$1") (pin "10") (pinfunction "IO19_10") (pintype "bidirectional"))
    )
    (net (code "203") (name "Net-(U$1-IO21)") (class "Default")
      (node (ref "I2C-PWM") (pin "4") (pinfunction "4_4") (pintype "passive"))
      (node (ref "I2C-PWM1") (pin "4") (pinfunction "4_4") (pintype "passive"))
      (node (ref "I2C-PWM2") (pin "4") (pinfunction "4_4") (pintype "passive"))
      (node (ref "I2C-PWM3") (pin "4") (pinfunction "4_4") (pintype "passive"))
      (node (ref "U$1") (pin "11") (pinfunction "IO21_11") (pintype "bidirectional"))
    )
    (net (code "204") (name "Net-(U$1-IO22)") (class "Default")
      (node (ref "I2C-PWM") (pin "3") (pinfunction "3_3") (pintype "passive"))
      (node (ref "I2C-PWM1") (pin "3") (pinfunction "3_3") (pintype "passive"))
      (node (ref "I2C-PWM2") (pin "3") (pinfunction "3_3") (pintype "passive"))
      (node (ref "I2C-PWM3") (pin "3") (pinfunction "3_3") (pintype "passive"))
      (node (ref "U$1") (pin "14") (pinfunction "IO22_14") (pintype "bidirectional"))
    )
    (net (code "205") (name "Net-(U$1-VIN)") (class "Default")
      (node (ref "I2C-PWM") (pin "5") (pinfunction "5_5") (pintype "passive"))
      (node (ref "I2C-PWM1") (pin "5") (pinfunction "5_5") (pintype "passive"))
      (node (ref "I2C-PWM2") (pin "5") (pinfunction "5_5") (pintype "passive"))
      (node (ref "I2C-PWM3") (pin "5") (pinfunction "5_5") (pintype "passive"))
      (node (ref "RELAY_BAR") (pin "10") (pinfunction "10_10") (pintype "passive"))
      (node (ref "U$1") (pin "30") (pinfunction "VIN_30") (pintype "bidirectional"))
      (node (ref "X1") (pin "4") (pinfunction "S_4") (pintype "passive"))
    )
    (net (code "206") (name "unconnected-(I2C-PWM-Pad2)") (class "Default")
      (node (ref "I2C-PWM") (pin "2") (pinfunction "2_2") (pintype "passive"))
    )
    (net (code "207") (name "unconnected-(I2C-PWM-Pad6)") (class "Default")
      (node (ref "I2C-PWM") (pin "6") (pinfunction "6_6") (pintype "passive"))
    )
    (net (code "208") (name "unconnected-(I2C-PWM1-Pad2)") (class "Default")
      (node (ref "I2C-PWM1") (pin "2") (pinfunction "2_2") (pintype "passive"))
    )
    (net (code "209") (name "unconnected-(I2C-PWM1-Pad6)") (class "Default")
      (node (ref "I2C-PWM1") (pin "6") (pinfunction "6_6") (pintype "passive"))
    )
    (net (code "210") (name "unconnected-(I2C-PWM2-Pad2)") (class "Default")
      (node (ref "I2C-PWM2") (pin "2") (pinfunction "2_2") (pintype "passive"))
    )
    (net (code "211") (name "unconnected-(I2C-PWM2-Pad6)") (class "Default")
      (node (ref "I2C-PWM2") (pin "6") (pinfunction "6_6") (pintype "passive"))
    )
    (net (code "212") (name "unconnected-(I2C-PWM3-Pad2)") (class "Default")
      (node (ref "I2C-PWM3") (pin "2") (pinfunction "2_2") (pintype "passive"))
    )
    (net (code "213") (name "unconnected-(I2C-PWM3-Pad6)") (class "Default")
      (node (ref "I2C-PWM3") (pin "6") (pinfunction "6_6") (pintype "passive"))
    )
    (net (code "214") (name "unconnected-(U$1-3V3-Pad1)") (class "Default")
      (node (ref "U$1") (pin "1") (pinfunction "3V3_1") (pintype "bidirectional"))
    )
    (net (code "215") (name "unconnected-(U$1-EN-Pad16)") (class "Default")
      (node (ref "U$1") (pin "16") (pinfunction "EN_16") (pintype "bidirectional"))
    )
    (net (code "216") (name "unconnected-(U$1-GND1-Pad28)") (class "Default")
      (node (ref "U$1") (pin "28") (pinfunction "GND1_28") (pintype "bidirectional"))
    )
    (net (code "217") (name "unconnected-(U$1-IO1-Pad13)") (class "Default")
      (node (ref "U$1") (pin "13") (pinfunction "IO1_13") (pintype "bidirectional"))
    )
    (net (code "218") (name "unconnected-(U$1-IO3-Pad12)") (class "Default")
      (node (ref "U$1") (pin "12") (pinfunction "IO3_12") (pintype "bidirectional"))
    )
    (net (code "219") (name "unconnected-(U$1-IO12-Pad27)") (class "Default")
      (node (ref "U$1") (pin "27") (pinfunction "IO12_27") (pintype "bidirectional"))
    )
    (net (code "220") (name "unconnected-(U$1-IO13-Pad28)") (class "Default")
      (node (ref "U$1") (pin "28") (pinfunction "IO13_28") (pintype "bidirectional"))
    )
    (net (code "221") (name "unconnected-(U$1-IO14-Pad26)") (class "Default")
      (node (ref "U$1") (pin "26") (pinfunction "IO14_26") (pintype "bidirectional"))
    )
    (net (code "222") (name "unconnected-(U$1-IO23-Pad15)") (class "Default")
      (node (ref "U$1") (pin "15") (pinfunction "IO23_15") (pintype "bidirectional"))
    )
    (net (code "223") (name "unconnected-(U$1-IO25-Pad23)") (class "Default")
      (node (ref "U$1") (pin "23") (pinfunction "IO25_23") (pintype "bidirectional"))
    )
    (net (code "224") (name "unconnected-(U$1-IO26-Pad24)") (class "Default")
      (node (ref "U$1") (pin "24") (pinfunction "IO26_24") (pintype "bidirectional"))
    )
    (net (code "225") (name "unconnected-(U$1-IO27-Pad24)") (class "Default")
      (node (ref "U$1") (pin "24") (pinfunction "IO27_24") (pintype "bidirectional"))
    )
    (net (code "226") (name "unconnected-(U$1-IO32-Pad21)") (class "Default")
      (node (ref "U$1") (pin "21") (pinfunction "IO32_21") (pintype "bidirectional"))
    )
    (net (code "227") (name "unconnected-(U$1-IO33-Pad22)") (class "Default")
      (node (ref "U$1") (pin "22") (pinfunction "IO33_22") (pintype "bidirectional"))
    )
    (net (code "228") (name "unconnected-(U$1-IO34-Pad19)") (class "Default")
      (node (ref "U$1") (pin "19") (pinfunction "IO34_19") (pintype "bidirectional"))
    )
    (net (code "229") (name "unconnected-(U$1-IO35-Pad20)") (class "Default")
      (node (ref "U$1") (pin "20") (pinfunction "IO35_20") (pintype "bidirectional"))
    )
    (net (code "230") (name "unconnected-(U$1-VN-Pad18)") (class "Default")
      (node (ref "U$1") (pin "18") (pinfunction "VN_18") (pintype "bidirectional"))
    )
    (net (code "231") (name "unconnected-(U$1-VP-Pad17)") (class "Default")
      (node (ref "U$1") (pin "17") (pinfunction "VP_17") (pintype "bidirectional"))
    )
  )
)
